# connect.net
KiCad netlist of a schematic drawn in Altium Designer
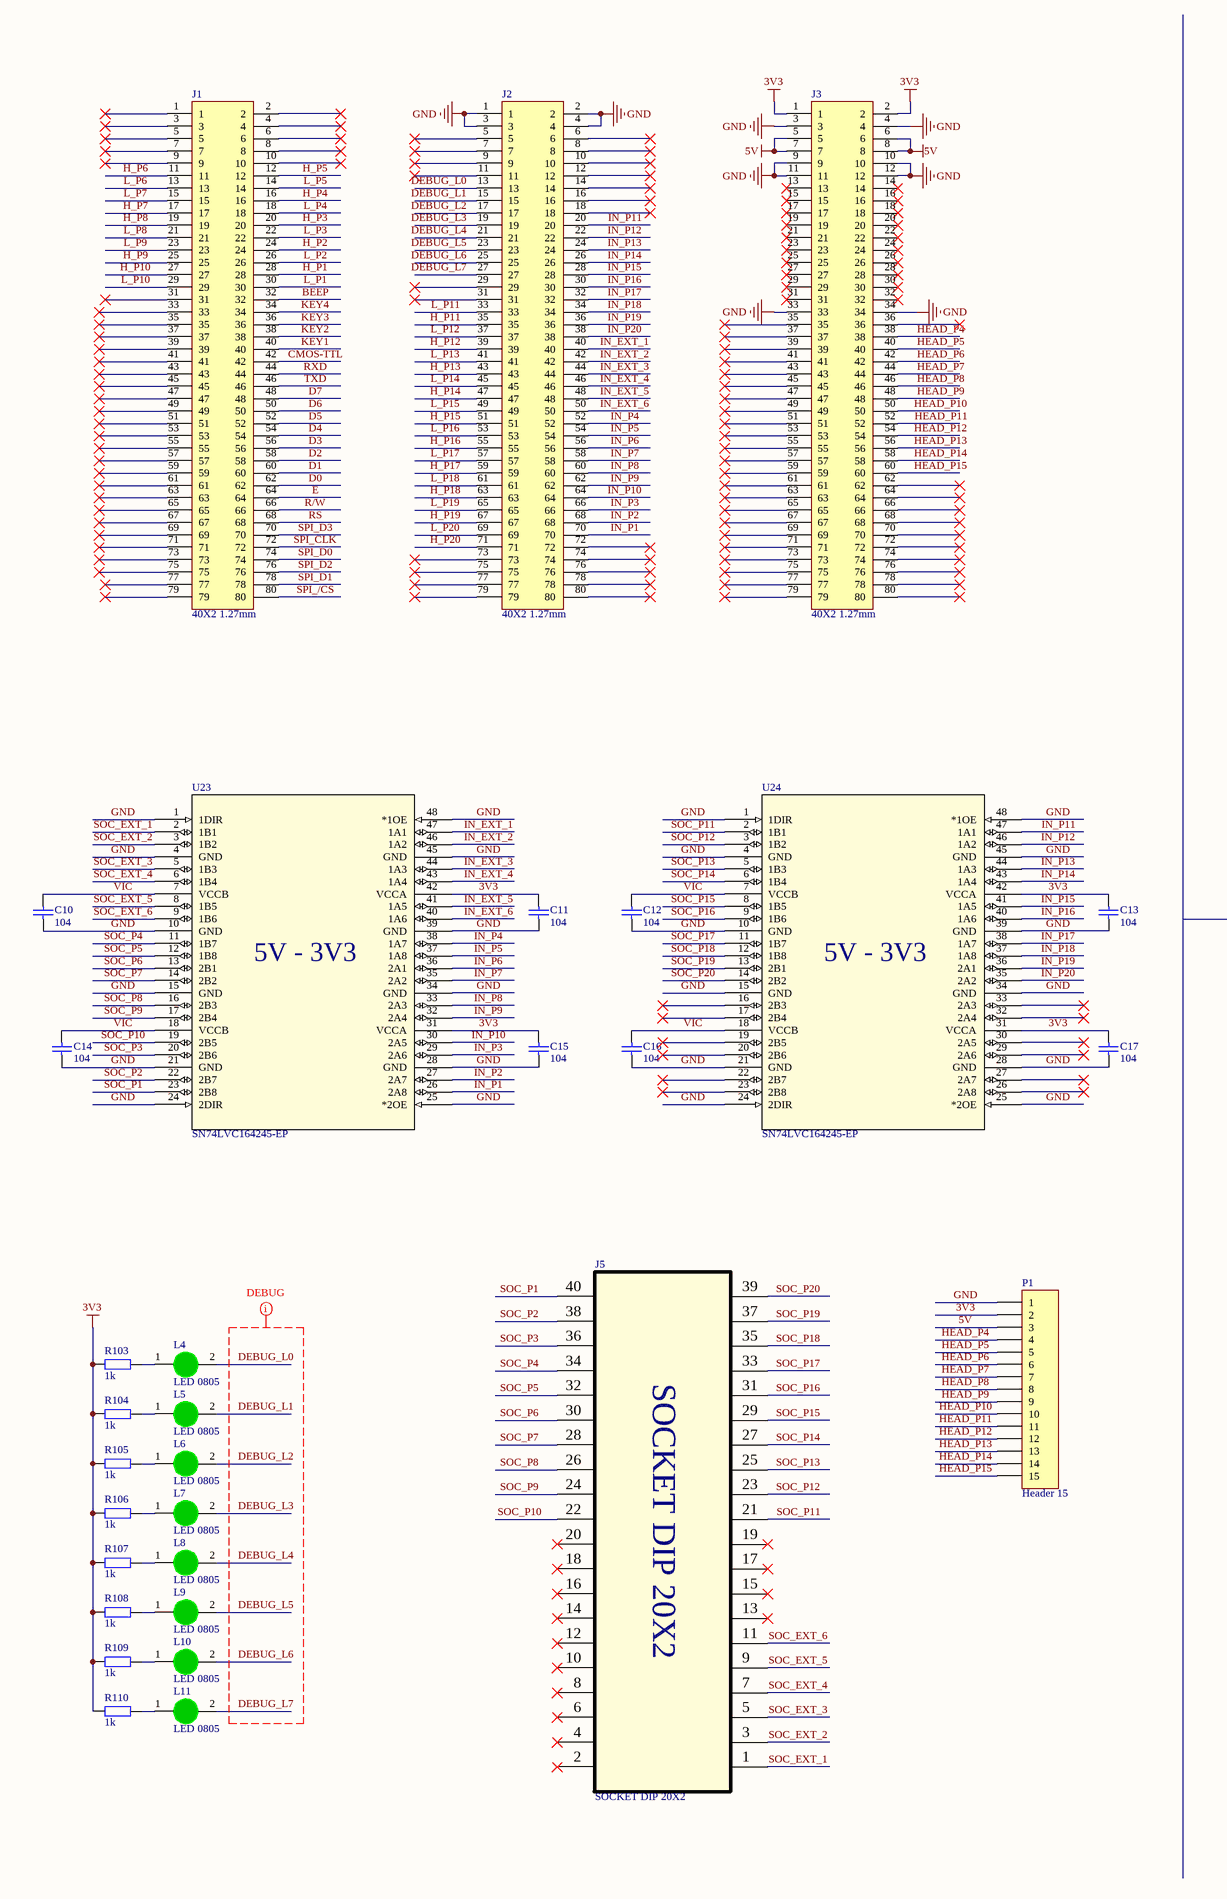
[diagram p0: connect.SchDoc, left]
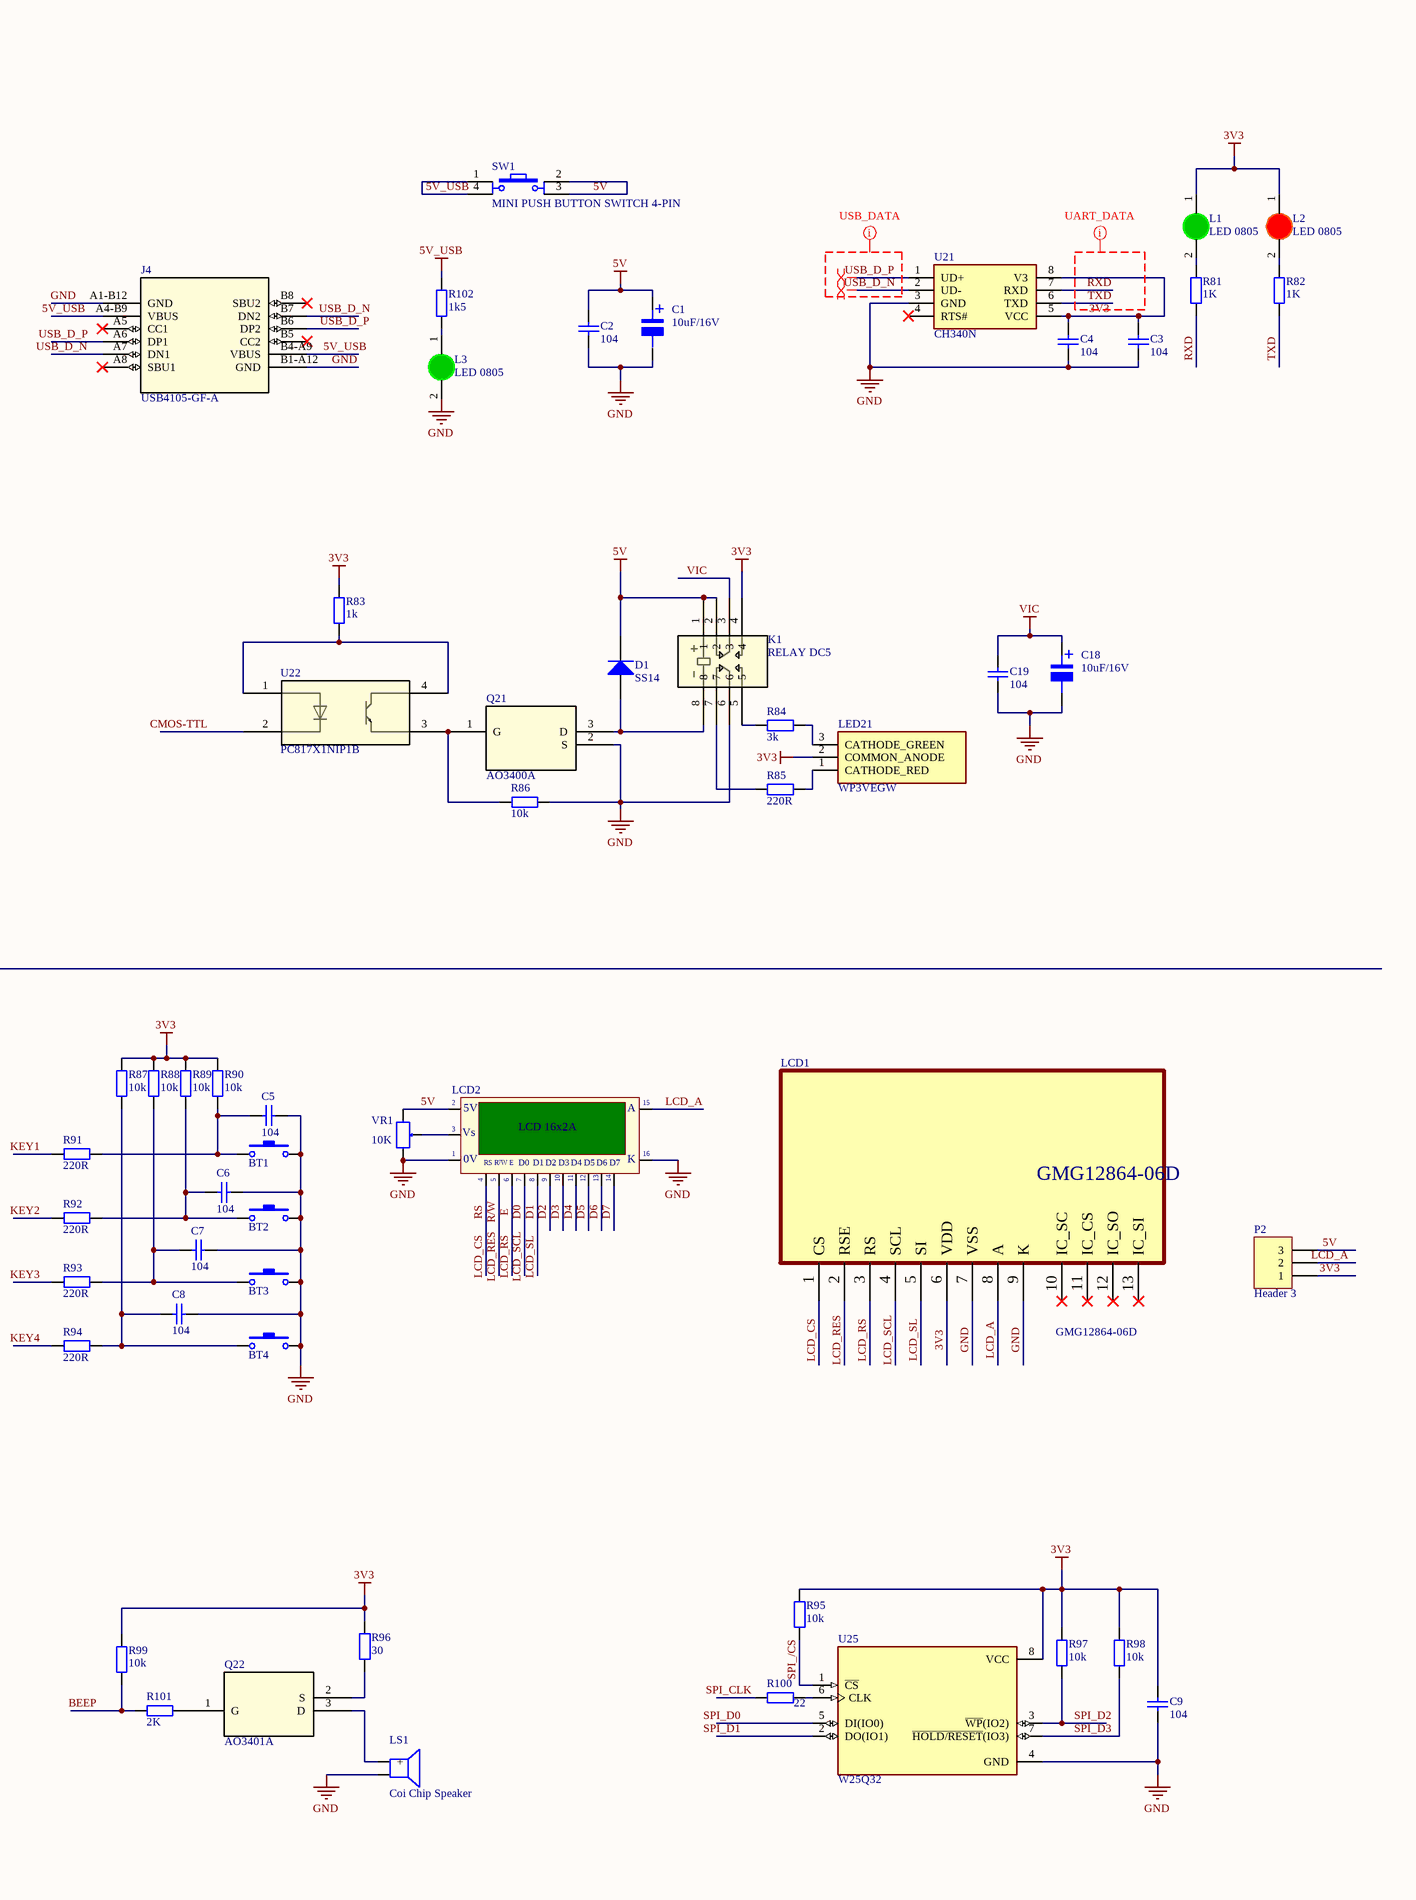
[diagram p1: connect.SchDoc, right]

(export (version "E")
  (design (tool "Eeschema 10.0.6"))
  (components
    (comp (ref "BT1")
      (value "Nut Nhan 2 Chan SMD 3x6x2.5")
      (footprint "Nut Nhan 2 Chan SMD 3x6x2.5")
      (libsource (lib "thuvien") (part "Nut Nhan 2 Chan SMD 3x6x2.5"))
    )
    (comp (ref "BT2")
      (value "Nut Nhan 2 Chan SMD 3x6x2.5")
      (footprint "Nut Nhan 2 Chan SMD 3x6x2.5")
      (libsource (lib "thuvien") (part "Nut Nhan 2 Chan SMD 3x6x2.5"))
    )
    (comp (ref "BT3")
      (value "Nut Nhan 2 Chan SMD 3x6x2.5")
      (footprint "Nut Nhan 2 Chan SMD 3x6x2.5")
      (libsource (lib "thuvien") (part "Nut Nhan 2 Chan SMD 3x6x2.5"))
    )
    (comp (ref "BT4")
      (value "Nut Nhan 2 Chan SMD 3x6x2.5")
      (footprint "Nut Nhan 2 Chan SMD 3x6x2.5")
      (libsource (lib "thuvien") (part "Nut Nhan 2 Chan SMD 3x6x2.5"))
    )
    (comp (ref "C1")
      (value "10uF/16V")
      (footprint "tu nhom 4 (b)")
      (description "Dán")
      (libsource (lib "thuvien") (part "Tu Nhom 10uF 16V"))
    )
    (comp (ref "C2")
      (value "104")
      (footprint "tu 0805")
      (description "Dán")
      (libsource (lib "thuvien") (part "Tu 0805 106 16V 10%"))
    )
    (comp (ref "C3")
      (value "104")
      (footprint "tu 0805")
      (description "Dán")
      (libsource (lib "thuvien") (part "Tu 0805 106 16V 10%"))
    )
    (comp (ref "C4")
      (value "104")
      (footprint "tu 0805")
      (description "Dán")
      (libsource (lib "thuvien") (part "Tu 0805 106 16V 10%"))
    )
    (comp (ref "C5")
      (value "104")
      (footprint "tu 0805")
      (description "Dán")
      (libsource (lib "thuvien") (part "Tu 0805 106 16V 10%"))
    )
    (comp (ref "C6")
      (value "104")
      (footprint "tu 0805")
      (description "Dán")
      (libsource (lib "thuvien") (part "Tu 0805 106 16V 10%"))
    )
    (comp (ref "C7")
      (value "104")
      (footprint "tu 0805")
      (description "Dán")
      (libsource (lib "thuvien") (part "Tu 0805 106 16V 10%"))
    )
    (comp (ref "C8")
      (value "104")
      (footprint "tu 0805")
      (description "Dán")
      (libsource (lib "thuvien") (part "Tu 0805 106 16V 10%"))
    )
    (comp (ref "C9")
      (value "104")
      (footprint "tu 0805")
      (description "Dán")
      (libsource (lib "thuvien") (part "Tu 0805 106 16V 10%"))
    )
    (comp (ref "C10")
      (value "104")
      (footprint "Tu 0805")
      (description "Dán")
      (libsource (lib "ThuVien") (part "Tu 104"))
    )
    (comp (ref "C11")
      (value "104")
      (footprint "Tu 0805")
      (description "Dán")
      (libsource (lib "ThuVien") (part "Tu 104"))
    )
    (comp (ref "C12")
      (value "104")
      (footprint "Tu 0805")
      (description "Dán")
      (libsource (lib "ThuVien") (part "Tu 104"))
    )
    (comp (ref "C13")
      (value "104")
      (footprint "Tu 0805")
      (description "Dán")
      (libsource (lib "ThuVien") (part "Tu 104"))
    )
    (comp (ref "C14")
      (value "104")
      (footprint "Tu 0805")
      (description "Dán")
      (libsource (lib "ThuVien") (part "Tu 104"))
    )
    (comp (ref "C15")
      (value "104")
      (footprint "Tu 0805")
      (description "Dán")
      (libsource (lib "ThuVien") (part "Tu 104"))
    )
    (comp (ref "C16")
      (value "104")
      (footprint "Tu 0805")
      (description "Dán")
      (libsource (lib "ThuVien") (part "Tu 104"))
    )
    (comp (ref "C17")
      (value "104")
      (footprint "Tu 0805")
      (description "Dán")
      (libsource (lib "ThuVien") (part "Tu 104"))
    )
    (comp (ref "C18")
      (value "10uF/16V")
      (footprint "tu nhom 4 (b)")
      (description "Dán")
      (libsource (lib "thuvien") (part "Tu Nhom 10uF 16V"))
    )
    (comp (ref "C19")
      (value "104")
      (footprint "tu 0805")
      (description "Dán")
      (libsource (lib "thuvien") (part "Tu 0805 106 16V 10%"))
    )
    (comp (ref "D1")
      (value "SS14")
      (footprint "DIODE SMA")
      (description "Dán")
      (libsource (lib "thuvien") (part "Diode SS14 ( 1N5819)"))
    )
    (comp (ref "J1")
      (value "40X2 1.27mm")
      (footprint "SOIC127P600X175-8N:CLP-140-02-XXX-D-A")
      (description "Connector")
      (fields (field (name "MANUFACTURER_PART_NUMBER") "CLP-140-02-G-D-A"))
      (libsource (lib "thuvien") (part "40X2 1.27mm"))
    )
    (comp (ref "J2")
      (value "40X2 1.27mm")
      (footprint "SOIC127P600X175-8N:CLP-140-02-XXX-D-A")
      (description "Connector")
      (fields (field (name "MANUFACTURER_PART_NUMBER") "CLP-140-02-G-D-A"))
      (libsource (lib "thuvien") (part "40X2 1.27mm"))
    )
    (comp (ref "J3")
      (value "40X2 1.27mm")
      (footprint "SOIC127P600X175-8N:CLP-140-02-XXX-D-A")
      (description "Connector")
      (fields (field (name "MANUFACTURER_PART_NUMBER") "CLP-140-02-G-D-A"))
      (libsource (lib "thuvien") (part "40X2 1.27mm"))
    )
    (comp (ref "J4")
      (value "USB4105-GF-A")
      (footprint "USB4105_GCT")
      (description "No Description Available")
      (fields (field (name "COPYRIGHT") "Copyright (C) 2023 Ultra Librarian. All rights reserved."))
      (libsource (lib "thuvien") (part "USB4105-GF-A"))
    )
    (comp (ref "J5")
      (value "SOCKET DIP 20X2")
      (footprint "CONN40_40-6554_ARS")
      (fields
        (field (name "MANUFACTURER_PART_NUMBER") "40-6554-10")
        (field (name "COPYRIGHT") "Copyright (C) 2023 Ultra Librarian. All rights reserved.")
      )
      (libsource (lib "thuvien") (part "SOCKET DIP 20X2"))
    )
    (comp (ref "K1")
      (value "RELAY DC5")
      (footprint "G6K-2F-Y DC3_OMR")
      (description "RELAY MINI")
      (fields
        (field (name "MANUFACTURER_PART_NUMBER") "G6K-2F-Y DC5")
        (field (name "COPYRIGHT") "Copyright (C) 2023 Ultra Librarian. All rights reserved.")
      )
      (libsource (lib "thuvien") (part "G6K-2F-Y DC5"))
    )
    (comp (ref "L1")
      (value "LED 0805")
      (footprint "LED-0805-Green")
      (description "Dán")
      (libsource (lib "thuvien") (part "LED 0805 Xanh La"))
    )
    (comp (ref "L2")
      (value "LED 0805")
      (footprint "LED-0805-Red")
      (description "Dán")
      (libsource (lib "thuvien") (part "LED 0805 Do"))
    )
    (comp (ref "L3")
      (value "LED 0805")
      (footprint "LED-0805-Green")
      (description "Dán")
      (libsource (lib "thuvien") (part "LED 0805 Xanh La"))
    )
    (comp (ref "L4")
      (value "LED 0805")
      (footprint "LED-0805-Green")
      (description "Dán")
      (libsource (lib "thuvien") (part "LED 0805 Xanh La"))
    )
    (comp (ref "L5")
      (value "LED 0805")
      (footprint "LED-0805-Green")
      (description "Dán")
      (libsource (lib "thuvien") (part "LED 0805 Xanh La"))
    )
    (comp (ref "L6")
      (value "LED 0805")
      (footprint "LED-0805-Green")
      (description "Dán")
      (libsource (lib "thuvien") (part "LED 0805 Xanh La"))
    )
    (comp (ref "L7")
      (value "LED 0805")
      (footprint "LED-0805-Green")
      (description "Dán")
      (libsource (lib "thuvien") (part "LED 0805 Xanh La"))
    )
    (comp (ref "L8")
      (value "LED 0805")
      (footprint "LED-0805-Green")
      (description "Dán")
      (libsource (lib "thuvien") (part "LED 0805 Xanh La"))
    )
    (comp (ref "L9")
      (value "LED 0805")
      (footprint "LED-0805-Green")
      (description "Dán")
      (libsource (lib "thuvien") (part "LED 0805 Xanh La"))
    )
    (comp (ref "L10")
      (value "LED 0805")
      (footprint "LED-0805-Green")
      (description "Dán")
      (libsource (lib "thuvien") (part "LED 0805 Xanh La"))
    )
    (comp (ref "L11")
      (value "LED 0805")
      (footprint "LED-0805-Green")
      (description "Dán")
      (libsource (lib "thuvien") (part "LED 0805 Xanh La"))
    )
    (comp (ref "LCD1")
      (value "GMG12864-06D")
      (footprint "GMG12864-06D")
      (fields (field (name "PUBLISHER") "Altium Limited"))
      (libsource (lib "thuvien") (part "GMG12864-06D"))
    )
    (comp (ref "LCD2")
      (value "LCD 16x2A")
      (footprint "LCD16X2N")
      (description "LCD dipslay 16 char, 2 line")
      (libsource (lib "thuvien") (part "LCD16x2A"))
    )
    (comp (ref "LED21")
      (value "WP3VEGW")
      (footprint "WP3VEGW")
      (description "LED RED/GREEN 3mm")
      (fields (field (name "MOUSER PART NUMBER") "604-WP3VEGW"))
      (libsource (lib "thuvien") (part "WP3VEGW"))
    )
    (comp (ref "LS1")
      (value "Coi Chip Speaker")
      (footprint "Coi Chip Speacker")
      (description "Còi chip")
      (libsource (lib "thuvien") (part "Coi Chip Speaker"))
    )
    (comp (ref "P1")
      (value "Header 15")
      (footprint "HDR1X15")
      (description "Header, 15-Pin")
      (fields (field (name "PUBLISHER") "Altium Limited"))
      (libsource (lib "Miscellaneous Connectors") (part "Header 15"))
    )
    (comp (ref "P2")
      (value "Header 3")
      (footprint "HDR1X3")
      (description "Header, 3-Pin")
      (fields (field (name "PUBLISHER") "Altium Limited"))
      (libsource (lib "Miscellaneous Connectors") (part "Header 3"))
    )
    (comp (ref "Q21")
      (value "AO3400A")
      (footprint "SOT-23-3L_AOS")
      (description "N-MOSFET")
      (fields (field (name "COPYRIGHT") "Copyright (C) 2023 Ultra Librarian. All rights reserved."))
      (libsource (lib "thuvien") (part "AO3400A"))
    )
    (comp (ref "Q22")
      (value "AO3401A")
      (footprint "SOT-23-3L_AOS")
      (description "P-MOSFET")
      (fields (field (name "COPYRIGHT") "Copyright (C) 2023 Ultra Librarian. All rights reserved."))
      (libsource (lib "thuvien") (part "AO3401A"))
    )
    (comp (ref "R81")
      (value "1K")
      (footprint "tro smd 0805")
      (description "Dán")
      (libsource (lib "thuvien") (part "Tro 0805 1% 10k"))
    )
    (comp (ref "R82")
      (value "1K")
      (footprint "tro smd 0805")
      (description "Dán")
      (libsource (lib "thuvien") (part "Tro 0805 1% 10k"))
    )
    (comp (ref "R83")
      (value "1k")
      (footprint "tro smd 0805")
      (description "Dán")
      (libsource (lib "thuvien") (part "Tro 0805 1% 10k"))
    )
    (comp (ref "R84")
      (value "3k")
      (footprint "tro smd 0805")
      (description "Dán")
      (libsource (lib "thuvien") (part "Tro 0805 1% 10k"))
    )
    (comp (ref "R85")
      (value "220R")
      (footprint "tro smd 0805")
      (description "Dán")
      (libsource (lib "thuvien") (part "Tro 0805 1% 10k"))
    )
    (comp (ref "R86")
      (value "10k")
      (footprint "tro smd 0805")
      (description "Dán")
      (libsource (lib "ThuVien") (part "Tro 0805 5% 10k"))
    )
    (comp (ref "R87")
      (value "10k")
      (footprint "tro smd 0805")
      (description "Dán")
      (libsource (lib "thuvien") (part "Tro 0805 1% 10k"))
    )
    (comp (ref "R88")
      (value "10k")
      (footprint "tro smd 0805")
      (description "Dán")
      (libsource (lib "thuvien") (part "Tro 0805 1% 10k"))
    )
    (comp (ref "R89")
      (value "10k")
      (footprint "tro smd 0805")
      (description "Dán")
      (libsource (lib "thuvien") (part "Tro 0805 1% 10k"))
    )
    (comp (ref "R90")
      (value "10k")
      (footprint "tro smd 0805")
      (description "Dán")
      (libsource (lib "thuvien") (part "Tro 0805 1% 10k"))
    )
    (comp (ref "R91")
      (value "220R")
      (footprint "tro smd 0805")
      (description "Dán")
      (libsource (lib "thuvien") (part "Tro 0805 1% 10k"))
    )
    (comp (ref "R92")
      (value "220R")
      (footprint "tro smd 0805")
      (description "Dán")
      (libsource (lib "thuvien") (part "Tro 0805 1% 10k"))
    )
    (comp (ref "R93")
      (value "220R")
      (footprint "tro smd 0805")
      (description "Dán")
      (libsource (lib "thuvien") (part "Tro 0805 1% 10k"))
    )
    (comp (ref "R94")
      (value "220R")
      (footprint "tro smd 0805")
      (description "Dán")
      (libsource (lib "thuvien") (part "Tro 0805 1% 10k"))
    )
    (comp (ref "R95")
      (value "10k")
      (footprint "tro smd 0805")
      (description "Dán")
      (libsource (lib "thuvien") (part "Tro 0805 1% 10k"))
    )
    (comp (ref "R96")
      (value "30")
      (footprint "tro smd 0805")
      (description "Dán")
      (libsource (lib "thuvien") (part "Tro 0805 1% 10k"))
    )
    (comp (ref "R97")
      (value "10k")
      (footprint "tro smd 0805")
      (description "Dán")
      (libsource (lib "thuvien") (part "Tro 0805 1% 10k"))
    )
    (comp (ref "R98")
      (value "10k")
      (footprint "tro smd 0805")
      (description "Dán")
      (libsource (lib "thuvien") (part "Tro 0805 1% 10k"))
    )
    (comp (ref "R99")
      (value "10k")
      (footprint "tro smd 0805")
      (description "Dán")
      (libsource (lib "thuvien") (part "Tro 0805 1% 10k"))
    )
    (comp (ref "R100")
      (value "22")
      (footprint "tro smd 0805")
      (description "Dán")
      (libsource (lib "thuvien") (part "Tro 0805 1% 10k"))
    )
    (comp (ref "R101")
      (value "2K")
      (footprint "tro smd 0805")
      (description "Dán")
      (libsource (lib "thuvien") (part "Tro 0805 1% 10k"))
    )
    (comp (ref "R102")
      (value "1k5")
      (footprint "tro smd 0805")
      (description "Dán")
      (libsource (lib "thuvien") (part "Tro 0805 1% 10k"))
    )
    (comp (ref "R103")
      (value "1k")
      (footprint "tro smd 0805")
      (description "Dán")
      (libsource (lib "thuvien") (part "Tro 0805 1% 10k"))
    )
    (comp (ref "R104")
      (value "1k")
      (footprint "tro smd 0805")
      (description "Dán")
      (libsource (lib "thuvien") (part "Tro 0805 1% 10k"))
    )
    (comp (ref "R105")
      (value "1k")
      (footprint "tro smd 0805")
      (description "Dán")
      (libsource (lib "thuvien") (part "Tro 0805 1% 10k"))
    )
    (comp (ref "R106")
      (value "1k")
      (footprint "tro smd 0805")
      (description "Dán")
      (libsource (lib "thuvien") (part "Tro 0805 1% 10k"))
    )
    (comp (ref "R107")
      (value "1k")
      (footprint "tro smd 0805")
      (description "Dán")
      (libsource (lib "thuvien") (part "Tro 0805 1% 10k"))
    )
    (comp (ref "R108")
      (value "1k")
      (footprint "tro smd 0805")
      (description "Dán")
      (libsource (lib "thuvien") (part "Tro 0805 1% 10k"))
    )
    (comp (ref "R109")
      (value "1k")
      (footprint "tro smd 0805")
      (description "Dán")
      (libsource (lib "thuvien") (part "Tro 0805 1% 10k"))
    )
    (comp (ref "R110")
      (value "1k")
      (footprint "tro smd 0805")
      (description "Dán")
      (libsource (lib "thuvien") (part "Tro 0805 1% 10k"))
    )
    (comp (ref "SW1")
      (value "MINI PUSH BUTTON SWITCH 4-PIN")
      (footprint "SW_70_31.5D47_TH_ST")
      (description "Tactile Switches MINI PUSH BUTTON SWITCH 4-PIN QTY. 4")
      (fields (field (name "MANUFACTURER") "Gravitech") (field (name "MANUFACTURER PART NUMBER") "BUTT-4"))
      (libsource (lib "thuvien") (part "SW2_BUTT-4-TH"))
    )
    (comp (ref "U21")
      (value "CH340N")
      (footprint "SOIC127P600X175-8N")
      (description "USB to TTL")
      (fields (field (name "MANUFACTURER_PART_NUMBER") "AO4606"))
      (libsource (lib "thuvien") (part "CH340N"))
    )
    (comp (ref "U22")
      (value "PC817X1NIP1B")
      (footprint "PC817XI_SHP")
      (description "cach ly quang")
      (fields (field (name "COPYRIGHT") "Copyright (C) 2023 Ultra Librarian. All rights reserved."))
      (libsource (lib "thuvien") (part "PC817X1NIP1B"))
    )
    (comp (ref "U23")
      (value "SN74LVC164245-EP")
      (footprint "DGG48")
      (description "3v3-5v, DIR enable")
      (fields
        (field (name "MANUFACTURER_PART_NUMBER") "CALVC164245MDGGREP")
        (field (name "COPYRIGHT") "Copyright (C) 2023 Ultra Librarian. All rights reserved.")
      )
      (libsource (lib "thuvien") (part "CALVC164245MDGGREP"))
    )
    (comp (ref "U24")
      (value "SN74LVC164245-EP")
      (footprint "DGG48")
      (description "3v3-5v, DIR enable")
      (fields
        (field (name "MANUFACTURER_PART_NUMBER") "CALVC164245MDGGREP")
        (field (name "COPYRIGHT") "Copyright (C) 2023 Ultra Librarian. All rights reserved.")
      )
      (libsource (lib "thuvien") (part "CALVC164245MDGGREP"))
    )
    (comp (ref "U25")
      (value "W25Q32")
      (footprint "WIN_SS-8_WIN")
      (description "3v 16m-Bit Serial Flash Memory With Dual")
      (fields
        (field (name "MF") "{'manufacturer': u'Winbond Electronics'}")
        (field (name "MP") "W25Q16JVSSIQ")
      )
      (libsource (lib "thuvien") (part "W25Q32"))
    )
    (comp (ref "VR1")
      (value "10K")
      (footprint "3362P_1")
      (description "Var Resistor")
      (libsource (lib "thuvien") (part "VR"))
    )
  )
  (nets
    (net (code "2") (name "/BEEP") (class "Default")
      (node (ref "J1") (pin "32") (pinfunction "32_32") (pintype "passive"))
      (node (ref "R101") (pin "1") (pinfunction "1_1") (pintype "passive"))
      (node (ref "R99") (pin "1") (pinfunction "1_1") (pintype "passive"))
    )
    (net (code "3") (name "/CMOS-TTL") (class "Default")
      (node (ref "J1") (pin "42") (pinfunction "42_42") (pintype "passive"))
      (node (ref "U22") (pin "2") (pinfunction "2_2") (pintype "passive"))
    )
    (net (code "4") (name "/D0") (class "Default")
      (node (ref "J1") (pin "62") (pinfunction "62_62") (pintype "passive"))
      (node (ref "LCD1") (pin "4") (pinfunction "SCL_4") (pintype "passive"))
      (node (ref "LCD2") (pin "7") (pinfunction "D0_7") (pintype "passive"))
    )
    (net (code "5") (name "/D1") (class "Default")
      (node (ref "J1") (pin "60") (pinfunction "60_60") (pintype "passive"))
      (node (ref "LCD1") (pin "5") (pinfunction "SI_5") (pintype "passive"))
      (node (ref "LCD2") (pin "8") (pinfunction "D1_8") (pintype "passive"))
    )
    (net (code "6") (name "/D2") (class "Default")
      (node (ref "J1") (pin "58") (pinfunction "58_58") (pintype "passive"))
      (node (ref "LCD2") (pin "9") (pinfunction "D2_9") (pintype "passive"))
    )
    (net (code "7") (name "/D3") (class "Default")
      (node (ref "J1") (pin "56") (pinfunction "56_56") (pintype "passive"))
      (node (ref "LCD2") (pin "10") (pinfunction "D3_10") (pintype "passive"))
    )
    (net (code "8") (name "/D4") (class "Default")
      (node (ref "J1") (pin "54") (pinfunction "54_54") (pintype "passive"))
      (node (ref "LCD2") (pin "11") (pinfunction "D4_11") (pintype "passive"))
    )
    (net (code "9") (name "/D5") (class "Default")
      (node (ref "J1") (pin "52") (pinfunction "52_52") (pintype "passive"))
      (node (ref "LCD2") (pin "12") (pinfunction "D5_12") (pintype "passive"))
    )
    (net (code "10") (name "/D6") (class "Default")
      (node (ref "J1") (pin "50") (pinfunction "50_50") (pintype "passive"))
      (node (ref "LCD2") (pin "13") (pinfunction "D6_13") (pintype "passive"))
    )
    (net (code "11") (name "/D7") (class "Default")
      (node (ref "J1") (pin "48") (pinfunction "48_48") (pintype "passive"))
      (node (ref "LCD2") (pin "14") (pinfunction "D7_14") (pintype "passive"))
    )
    (net (code "12") (name "/DEBUG_L0") (class "Default")
      (node (ref "J2") (pin "13") (pinfunction "13_13") (pintype "passive"))
      (node (ref "L4") (pin "2") (pinfunction "K_2") (pintype "passive"))
    )
    (net (code "13") (name "/DEBUG_L1") (class "Default")
      (node (ref "J2") (pin "15") (pinfunction "15_15") (pintype "passive"))
      (node (ref "L5") (pin "2") (pinfunction "K_2") (pintype "passive"))
    )
    (net (code "14") (name "/DEBUG_L2") (class "Default")
      (node (ref "J2") (pin "17") (pinfunction "17_17") (pintype "passive"))
      (node (ref "L6") (pin "2") (pinfunction "K_2") (pintype "passive"))
    )
    (net (code "15") (name "/DEBUG_L3") (class "Default")
      (node (ref "J2") (pin "19") (pinfunction "19_19") (pintype "passive"))
      (node (ref "L7") (pin "2") (pinfunction "K_2") (pintype "passive"))
    )
    (net (code "16") (name "/DEBUG_L4") (class "Default")
      (node (ref "J2") (pin "21") (pinfunction "21_21") (pintype "passive"))
      (node (ref "L8") (pin "2") (pinfunction "K_2") (pintype "passive"))
    )
    (net (code "17") (name "/DEBUG_L5") (class "Default")
      (node (ref "J2") (pin "23") (pinfunction "23_23") (pintype "passive"))
      (node (ref "L9") (pin "2") (pinfunction "K_2") (pintype "passive"))
    )
    (net (code "18") (name "/DEBUG_L6") (class "Default")
      (node (ref "J2") (pin "25") (pinfunction "25_25") (pintype "passive"))
      (node (ref "L10") (pin "2") (pinfunction "K_2") (pintype "passive"))
    )
    (net (code "19") (name "/DEBUG_L7") (class "Default")
      (node (ref "J2") (pin "27") (pinfunction "27_27") (pintype "passive"))
      (node (ref "L11") (pin "2") (pinfunction "K_2") (pintype "passive"))
    )
    (net (code "20") (name "/E") (class "Default")
      (node (ref "J1") (pin "64") (pinfunction "64_64") (pintype "passive"))
      (node (ref "LCD1") (pin "3") (pinfunction "RS_3") (pintype "passive"))
      (node (ref "LCD2") (pin "6") (pinfunction "~{EN}_6") (pintype "passive"))
    )
    (net (code "21") (name "/HEAD_P4") (class "Default")
      (node (ref "J3") (pin "38") (pinfunction "38_38") (pintype "passive"))
      (node (ref "P1") (pin "4") (pinfunction "4_4") (pintype "passive"))
    )
    (net (code "22") (name "/HEAD_P5") (class "Default")
      (node (ref "J3") (pin "40") (pinfunction "40_40") (pintype "passive"))
      (node (ref "P1") (pin "5") (pinfunction "5_5") (pintype "passive"))
    )
    (net (code "23") (name "/HEAD_P6") (class "Default")
      (node (ref "J3") (pin "42") (pinfunction "42_42") (pintype "passive"))
      (node (ref "P1") (pin "6") (pinfunction "6_6") (pintype "passive"))
    )
    (net (code "24") (name "/HEAD_P7") (class "Default")
      (node (ref "J3") (pin "44") (pinfunction "44_44") (pintype "passive"))
      (node (ref "P1") (pin "7") (pinfunction "7_7") (pintype "passive"))
    )
    (net (code "25") (name "/HEAD_P8") (class "Default")
      (node (ref "J3") (pin "46") (pinfunction "46_46") (pintype "passive"))
      (node (ref "P1") (pin "8") (pinfunction "8_8") (pintype "passive"))
    )
    (net (code "26") (name "/HEAD_P9") (class "Default")
      (node (ref "J3") (pin "48") (pinfunction "48_48") (pintype "passive"))
      (node (ref "P1") (pin "9") (pinfunction "9_9") (pintype "passive"))
    )
    (net (code "27") (name "/HEAD_P10") (class "Default")
      (node (ref "J3") (pin "50") (pinfunction "50_50") (pintype "passive"))
      (node (ref "P1") (pin "10") (pinfunction "10_10") (pintype "passive"))
    )
    (net (code "28") (name "/HEAD_P11") (class "Default")
      (node (ref "J3") (pin "52") (pinfunction "52_52") (pintype "passive"))
      (node (ref "P1") (pin "11") (pinfunction "11_11") (pintype "passive"))
    )
    (net (code "29") (name "/HEAD_P12") (class "Default")
      (node (ref "J3") (pin "54") (pinfunction "54_54") (pintype "passive"))
      (node (ref "P1") (pin "12") (pinfunction "12_12") (pintype "passive"))
    )
    (net (code "30") (name "/HEAD_P13") (class "Default")
      (node (ref "J3") (pin "56") (pinfunction "56_56") (pintype "passive"))
      (node (ref "P1") (pin "13") (pinfunction "13_13") (pintype "passive"))
    )
    (net (code "31") (name "/HEAD_P14") (class "Default")
      (node (ref "J3") (pin "58") (pinfunction "58_58") (pintype "passive"))
      (node (ref "P1") (pin "14") (pinfunction "14_14") (pintype "passive"))
    )
    (net (code "32") (name "/HEAD_P15") (class "Default")
      (node (ref "J3") (pin "60") (pinfunction "60_60") (pintype "passive"))
      (node (ref "P1") (pin "15") (pinfunction "15_15") (pintype "passive"))
    )
    (net (code "33") (name "/H_P1") (class "Default")
      (node (ref "J1") (pin "28") (pinfunction "28_28") (pintype "passive"))
    )
    (net (code "34") (name "/H_P2") (class "Default")
      (node (ref "J1") (pin "24") (pinfunction "24_24") (pintype "passive"))
    )
    (net (code "35") (name "/H_P3") (class "Default")
      (node (ref "J1") (pin "20") (pinfunction "20_20") (pintype "passive"))
    )
    (net (code "36") (name "/H_P4") (class "Default")
      (node (ref "J1") (pin "16") (pinfunction "16_16") (pintype "passive"))
    )
    (net (code "37") (name "/H_P5") (class "Default")
      (node (ref "J1") (pin "12") (pinfunction "12_12") (pintype "passive"))
    )
    (net (code "38") (name "/H_P6") (class "Default")
      (node (ref "J1") (pin "11") (pinfunction "11_11") (pintype "passive"))
    )
    (net (code "39") (name "/H_P7") (class "Default")
      (node (ref "J1") (pin "17") (pinfunction "17_17") (pintype "passive"))
    )
    (net (code "40") (name "/H_P8") (class "Default")
      (node (ref "J1") (pin "19") (pinfunction "19_19") (pintype "passive"))
    )
    (net (code "41") (name "/H_P9") (class "Default")
      (node (ref "J1") (pin "25") (pinfunction "25_25") (pintype "passive"))
    )
    (net (code "42") (name "/H_P10") (class "Default")
      (node (ref "J1") (pin "27") (pinfunction "27_27") (pintype "passive"))
    )
    (net (code "43") (name "/H_P11") (class "Default")
      (node (ref "J2") (pin "35") (pinfunction "35_35") (pintype "passive"))
    )
    (net (code "44") (name "/H_P12") (class "Default")
      (node (ref "J2") (pin "39") (pinfunction "39_39") (pintype "passive"))
    )
    (net (code "45") (name "/H_P13") (class "Default")
      (node (ref "J2") (pin "43") (pinfunction "43_43") (pintype "passive"))
    )
    (net (code "46") (name "/H_P14") (class "Default")
      (node (ref "J2") (pin "47") (pinfunction "47_47") (pintype "passive"))
    )
    (net (code "47") (name "/H_P15") (class "Default")
      (node (ref "J2") (pin "51") (pinfunction "51_51") (pintype "passive"))
    )
    (net (code "48") (name "/H_P16") (class "Default")
      (node (ref "J2") (pin "55") (pinfunction "55_55") (pintype "passive"))
    )
    (net (code "49") (name "/H_P17") (class "Default")
      (node (ref "J2") (pin "59") (pinfunction "59_59") (pintype "passive"))
    )
    (net (code "50") (name "/H_P18") (class "Default")
      (node (ref "J2") (pin "63") (pinfunction "63_63") (pintype "passive"))
    )
    (net (code "51") (name "/H_P19") (class "Default")
      (node (ref "J2") (pin "67") (pinfunction "67_67") (pintype "passive"))
    )
    (net (code "52") (name "/H_P20") (class "Default")
      (node (ref "J2") (pin "71") (pinfunction "71_71") (pintype "passive"))
    )
    (net (code "53") (name "/IN_EXT_1") (class "Default")
      (node (ref "J2") (pin "40") (pinfunction "40_40") (pintype "passive"))
      (node (ref "U23") (pin "47") (pinfunction "1A1_47") (pintype "bidirectional"))
    )
    (net (code "54") (name "/IN_EXT_2") (class "Default")
      (node (ref "J2") (pin "42") (pinfunction "42_42") (pintype "passive"))
      (node (ref "U23") (pin "46") (pinfunction "1A2_46") (pintype "bidirectional"))
    )
    (net (code "55") (name "/IN_EXT_3") (class "Default")
      (node (ref "J2") (pin "44") (pinfunction "44_44") (pintype "passive"))
      (node (ref "U23") (pin "44") (pinfunction "1A3_44") (pintype "bidirectional"))
    )
    (net (code "56") (name "/IN_EXT_4") (class "Default")
      (node (ref "J2") (pin "46") (pinfunction "46_46") (pintype "passive"))
      (node (ref "U23") (pin "43") (pinfunction "1A4_43") (pintype "bidirectional"))
    )
    (net (code "57") (name "/IN_EXT_5") (class "Default")
      (node (ref "J2") (pin "48") (pinfunction "48_48") (pintype "passive"))
      (node (ref "U23") (pin "41") (pinfunction "1A5_41") (pintype "bidirectional"))
    )
    (net (code "58") (name "/IN_EXT_6") (class "Default")
      (node (ref "J2") (pin "50") (pinfunction "50_50") (pintype "passive"))
      (node (ref "U23") (pin "40") (pinfunction "1A6_40") (pintype "bidirectional"))
    )
    (net (code "59") (name "/IN_P1") (class "Default")
      (node (ref "J2") (pin "70") (pinfunction "70_70") (pintype "passive"))
      (node (ref "U23") (pin "26") (pinfunction "2A8_26") (pintype "bidirectional"))
    )
    (net (code "60") (name "/IN_P2") (class "Default")
      (node (ref "J2") (pin "68") (pinfunction "68_68") (pintype "passive"))
      (node (ref "U23") (pin "27") (pinfunction "2A7_27") (pintype "bidirectional"))
    )
    (net (code "61") (name "/IN_P3") (class "Default")
      (node (ref "J2") (pin "66") (pinfunction "66_66") (pintype "passive"))
      (node (ref "U23") (pin "29") (pinfunction "2A6_29") (pintype "bidirectional"))
    )
    (net (code "62") (name "/IN_P4") (class "Default")
      (node (ref "J2") (pin "52") (pinfunction "52_52") (pintype "passive"))
      (node (ref "U23") (pin "38") (pinfunction "1A7_38") (pintype "bidirectional"))
    )
    (net (code "63") (name "/IN_P5") (class "Default")
      (node (ref "J2") (pin "54") (pinfunction "54_54") (pintype "passive"))
      (node (ref "U23") (pin "37") (pinfunction "1A8_37") (pintype "bidirectional"))
    )
    (net (code "64") (name "/IN_P6") (class "Default")
      (node (ref "J2") (pin "56") (pinfunction "56_56") (pintype "passive"))
      (node (ref "U23") (pin "36") (pinfunction "2A1_36") (pintype "bidirectional"))
    )
    (net (code "65") (name "/IN_P7") (class "Default")
      (node (ref "J2") (pin "58") (pinfunction "58_58") (pintype "passive"))
      (node (ref "U23") (pin "35") (pinfunction "2A2_35") (pintype "bidirectional"))
    )
    (net (code "66") (name "/IN_P8") (class "Default")
      (node (ref "J2") (pin "60") (pinfunction "60_60") (pintype "passive"))
      (node (ref "U23") (pin "33") (pinfunction "2A3_33") (pintype "bidirectional"))
    )
    (net (code "67") (name "/IN_P9") (class "Default")
      (node (ref "J2") (pin "62") (pinfunction "62_62") (pintype "passive"))
      (node (ref "U23") (pin "32") (pinfunction "2A4_32") (pintype "bidirectional"))
    )
    (net (code "68") (name "/IN_P10") (class "Default")
      (node (ref "J2") (pin "64") (pinfunction "64_64") (pintype "passive"))
      (node (ref "U23") (pin "30") (pinfunction "2A5_30") (pintype "bidirectional"))
    )
    (net (code "69") (name "/IN_P11") (class "Default")
      (node (ref "J2") (pin "20") (pinfunction "20_20") (pintype "passive"))
      (node (ref "U24") (pin "47") (pinfunction "1A1_47") (pintype "bidirectional"))
    )
    (net (code "70") (name "/IN_P12") (class "Default")
      (node (ref "J2") (pin "22") (pinfunction "22_22") (pintype "passive"))
      (node (ref "U24") (pin "46") (pinfunction "1A2_46") (pintype "bidirectional"))
    )
    (net (code "71") (name "/IN_P13") (class "Default")
      (node (ref "J2") (pin "24") (pinfunction "24_24") (pintype "passive"))
      (node (ref "U24") (pin "44") (pinfunction "1A3_44") (pintype "bidirectional"))
    )
    (net (code "72") (name "/IN_P14") (class "Default")
      (node (ref "J2") (pin "26") (pinfunction "26_26") (pintype "passive"))
      (node (ref "U24") (pin "43") (pinfunction "1A4_43") (pintype "bidirectional"))
    )
    (net (code "73") (name "/IN_P15") (class "Default")
      (node (ref "J2") (pin "28") (pinfunction "28_28") (pintype "passive"))
      (node (ref "U24") (pin "41") (pinfunction "1A5_41") (pintype "bidirectional"))
    )
    (net (code "74") (name "/IN_P16") (class "Default")
      (node (ref "J2") (pin "30") (pinfunction "30_30") (pintype "passive"))
      (node (ref "U24") (pin "40") (pinfunction "1A6_40") (pintype "bidirectional"))
    )
    (net (code "75") (name "/IN_P17") (class "Default")
      (node (ref "J2") (pin "32") (pinfunction "32_32") (pintype "passive"))
      (node (ref "U24") (pin "38") (pinfunction "1A7_38") (pintype "bidirectional"))
    )
    (net (code "76") (name "/IN_P18") (class "Default")
      (node (ref "J2") (pin "34") (pinfunction "34_34") (pintype "passive"))
      (node (ref "U24") (pin "37") (pinfunction "1A8_37") (pintype "bidirectional"))
    )
    (net (code "77") (name "/IN_P19") (class "Default")
      (node (ref "J2") (pin "36") (pinfunction "36_36") (pintype "passive"))
      (node (ref "U24") (pin "36") (pinfunction "2A1_36") (pintype "bidirectional"))
    )
    (net (code "78") (name "/IN_P20") (class "Default")
      (node (ref "J2") (pin "38") (pinfunction "38_38") (pintype "passive"))
      (node (ref "U24") (pin "35") (pinfunction "2A2_35") (pintype "bidirectional"))
    )
    (net (code "79") (name "/KEY1") (class "Default")
      (node (ref "J1") (pin "40") (pinfunction "40_40") (pintype "passive"))
      (node (ref "R91") (pin "1") (pinfunction "1_1") (pintype "passive"))
    )
    (net (code "80") (name "/KEY2") (class "Default")
      (node (ref "J1") (pin "38") (pinfunction "38_38") (pintype "passive"))
      (node (ref "R92") (pin "1") (pinfunction "1_1") (pintype "passive"))
    )
    (net (code "81") (name "/KEY3") (class "Default")
      (node (ref "J1") (pin "36") (pinfunction "36_36") (pintype "passive"))
      (node (ref "R93") (pin "1") (pinfunction "1_1") (pintype "passive"))
    )
    (net (code "82") (name "/KEY4") (class "Default")
      (node (ref "J1") (pin "34") (pinfunction "34_34") (pintype "passive"))
      (node (ref "R94") (pin "1") (pinfunction "1_1") (pintype "passive"))
    )
    (net (code "83") (name "/LCD_A") (class "Default")
      (node (ref "LCD1") (pin "8") (pinfunction "A_8") (pintype "passive"))
      (node (ref "LCD2") (pin "15") (pinfunction "A_15") (pintype "passive"))
      (node (ref "P2") (pin "2") (pinfunction "2_2") (pintype "passive"))
    )
    (net (code "84") (name "/LCD_CS") (class "Default")
      (node (ref "J1") (pin "68") (pinfunction "68_68") (pintype "passive"))
      (node (ref "LCD1") (pin "1") (pinfunction "CS_1") (pintype "passive"))
      (node (ref "LCD2") (pin "4") (pinfunction "RS_4") (pintype "passive"))
    )
    (net (code "85") (name "/LCD_RES") (class "Default")
      (node (ref "J1") (pin "66") (pinfunction "66_66") (pintype "passive"))
      (node (ref "LCD1") (pin "2") (pinfunction "RSE_2") (pintype "passive"))
      (node (ref "LCD2") (pin "5") (pinfunction "R/~{W}_5") (pintype "passive"))
    )
    (net (code "86") (name "/L_P1") (class "Default")
      (node (ref "J1") (pin "30") (pinfunction "30_30") (pintype "passive"))
    )
    (net (code "87") (name "/L_P2") (class "Default")
      (node (ref "J1") (pin "26") (pinfunction "26_26") (pintype "passive"))
    )
    (net (code "88") (name "/L_P3") (class "Default")
      (node (ref "J1") (pin "22") (pinfunction "22_22") (pintype "passive"))
    )
    (net (code "89") (name "/L_P4") (class "Default")
      (node (ref "J1") (pin "18") (pinfunction "18_18") (pintype "passive"))
    )
    (net (code "90") (name "/L_P5") (class "Default")
      (node (ref "J1") (pin "14") (pinfunction "14_14") (pintype "passive"))
    )
    (net (code "91") (name "/L_P6") (class "Default")
      (node (ref "J1") (pin "13") (pinfunction "13_13") (pintype "passive"))
    )
    (net (code "92") (name "/L_P7") (class "Default")
      (node (ref "J1") (pin "15") (pinfunction "15_15") (pintype "passive"))
    )
    (net (code "93") (name "/L_P8") (class "Default")
      (node (ref "J1") (pin "21") (pinfunction "21_21") (pintype "passive"))
    )
    (net (code "94") (name "/L_P9") (class "Default")
      (node (ref "J1") (pin "23") (pinfunction "23_23") (pintype "passive"))
    )
    (net (code "95") (name "/L_P10") (class "Default")
      (node (ref "J1") (pin "29") (pinfunction "29_29") (pintype "passive"))
    )
    (net (code "96") (name "/L_P11") (class "Default")
      (node (ref "J2") (pin "33") (pinfunction "33_33") (pintype "passive"))
    )
    (net (code "97") (name "/L_P12") (class "Default")
      (node (ref "J2") (pin "37") (pinfunction "37_37") (pintype "passive"))
    )
    (net (code "98") (name "/L_P13") (class "Default")
      (node (ref "J2") (pin "41") (pinfunction "41_41") (pintype "passive"))
    )
    (net (code "99") (name "/L_P14") (class "Default")
      (node (ref "J2") (pin "45") (pinfunction "45_45") (pintype "passive"))
    )
    (net (code "100") (name "/L_P15") (class "Default")
      (node (ref "J2") (pin "49") (pinfunction "49_49") (pintype "passive"))
    )
    (net (code "101") (name "/L_P16") (class "Default")
      (node (ref "J2") (pin "53") (pinfunction "53_53") (pintype "passive"))
    )
    (net (code "102") (name "/L_P17") (class "Default")
      (node (ref "J2") (pin "57") (pinfunction "57_57") (pintype "passive"))
    )
    (net (code "103") (name "/L_P18") (class "Default")
      (node (ref "J2") (pin "61") (pinfunction "61_61") (pintype "passive"))
    )
    (net (code "104") (name "/L_P19") (class "Default")
      (node (ref "J2") (pin "65") (pinfunction "65_65") (pintype "passive"))
    )
    (net (code "105") (name "/L_P20") (class "Default")
      (node (ref "J2") (pin "69") (pinfunction "69_69") (pintype "passive"))
    )
    (net (code "106") (name "/RXD") (class "Default")
      (node (ref "J1") (pin "44") (pinfunction "44_44") (pintype "passive"))
      (node (ref "R81") (pin "2") (pinfunction "2_2") (pintype "passive"))
      (node (ref "U21") (pin "7") (pinfunction "RXD_7") (pintype "passive"))
    )
    (net (code "107") (name "/SOC_EXT_1") (class "Default")
      (node (ref "J5") (pin "1") (pintype "passive"))
      (node (ref "U23") (pin "2") (pinfunction "1B1_2") (pintype "bidirectional"))
    )
    (net (code "108") (name "/SOC_EXT_2") (class "Default")
      (node (ref "J5") (pin "3") (pintype "passive"))
      (node (ref "U23") (pin "3") (pinfunction "1B2_3") (pintype "bidirectional"))
    )
    (net (code "109") (name "/SOC_EXT_3") (class "Default")
      (node (ref "J5") (pin "5") (pintype "passive"))
      (node (ref "U23") (pin "5") (pinfunction "1B3_5") (pintype "bidirectional"))
    )
    (net (code "110") (name "/SOC_EXT_4") (class "Default")
      (node (ref "J5") (pin "7") (pintype "passive"))
      (node (ref "U23") (pin "6") (pinfunction "1B4_6") (pintype "bidirectional"))
    )
    (net (code "111") (name "/SOC_EXT_5") (class "Default")
      (node (ref "J5") (pin "9") (pintype "passive"))
      (node (ref "U23") (pin "8") (pinfunction "1B5_8") (pintype "bidirectional"))
    )
    (net (code "112") (name "/SOC_EXT_6") (class "Default")
      (node (ref "J5") (pin "11") (pintype "passive"))
      (node (ref "U23") (pin "9") (pinfunction "1B6_9") (pintype "bidirectional"))
    )
    (net (code "113") (name "/SOC_P1") (class "Default")
      (node (ref "J5") (pin "40") (pintype "passive"))
      (node (ref "U23") (pin "23") (pinfunction "2B8_23") (pintype "bidirectional"))
    )
    (net (code "114") (name "/SOC_P2") (class "Default")
      (node (ref "J5") (pin "38") (pintype "passive"))
      (node (ref "U23") (pin "22") (pinfunction "2B7_22") (pintype "bidirectional"))
    )
    (net (code "115") (name "/SOC_P3") (class "Default")
      (node (ref "J5") (pin "36") (pintype "passive"))
      (node (ref "U23") (pin "20") (pinfunction "2B6_20") (pintype "bidirectional"))
    )
    (net (code "116") (name "/SOC_P4") (class "Default")
      (node (ref "J5") (pin "34") (pintype "passive"))
      (node (ref "U23") (pin "11") (pinfunction "1B7_11") (pintype "bidirectional"))
    )
    (net (code "117") (name "/SOC_P5") (class "Default")
      (node (ref "J5") (pin "32") (pintype "passive"))
      (node (ref "U23") (pin "12") (pinfunction "1B8_12") (pintype "bidirectional"))
    )
    (net (code "118") (name "/SOC_P6") (class "Default")
      (node (ref "J5") (pin "30") (pintype "passive"))
      (node (ref "U23") (pin "13") (pinfunction "2B1_13") (pintype "bidirectional"))
    )
    (net (code "119") (name "/SOC_P7") (class "Default")
      (node (ref "J5") (pin "28") (pintype "passive"))
      (node (ref "U23") (pin "14") (pinfunction "2B2_14") (pintype "bidirectional"))
    )
    (net (code "120") (name "/SOC_P8") (class "Default")
      (node (ref "J5") (pin "26") (pintype "passive"))
      (node (ref "U23") (pin "16") (pinfunction "2B3_16") (pintype "bidirectional"))
    )
    (net (code "121") (name "/SOC_P9") (class "Default")
      (node (ref "J5") (pin "24") (pintype "passive"))
      (node (ref "U23") (pin "17") (pinfunction "2B4_17") (pintype "bidirectional"))
    )
    (net (code "122") (name "/SOC_P10") (class "Default")
      (node (ref "J5") (pin "22") (pintype "passive"))
      (node (ref "U23") (pin "19") (pinfunction "2B5_19") (pintype "bidirectional"))
    )
    (net (code "123") (name "/SOC_P11") (class "Default")
      (node (ref "J5") (pin "21") (pintype "passive"))
      (node (ref "U24") (pin "2") (pinfunction "1B1_2") (pintype "bidirectional"))
    )
    (net (code "124") (name "/SOC_P12") (class "Default")
      (node (ref "J5") (pin "23") (pintype "passive"))
      (node (ref "U24") (pin "3") (pinfunction "1B2_3") (pintype "bidirectional"))
    )
    (net (code "125") (name "/SOC_P13") (class "Default")
      (node (ref "J5") (pin "25") (pintype "passive"))
      (node (ref "U24") (pin "5") (pinfunction "1B3_5") (pintype "bidirectional"))
    )
    (net (code "126") (name "/SOC_P14") (class "Default")
      (node (ref "J5") (pin "27") (pintype "passive"))
      (node (ref "U24") (pin "6") (pinfunction "1B4_6") (pintype "bidirectional"))
    )
    (net (code "127") (name "/SOC_P15") (class "Default")
      (node (ref "J5") (pin "29") (pintype "passive"))
      (node (ref "U24") (pin "8") (pinfunction "1B5_8") (pintype "bidirectional"))
    )
    (net (code "128") (name "/SOC_P16") (class "Default")
      (node (ref "J5") (pin "31") (pintype "passive"))
      (node (ref "U24") (pin "9") (pinfunction "1B6_9") (pintype "bidirectional"))
    )
    (net (code "129") (name "/SOC_P17") (class "Default")
      (node (ref "J5") (pin "33") (pintype "passive"))
      (node (ref "U24") (pin "11") (pinfunction "1B7_11") (pintype "bidirectional"))
    )
    (net (code "130") (name "/SOC_P18") (class "Default")
      (node (ref "J5") (pin "35") (pintype "passive"))
      (node (ref "U24") (pin "12") (pinfunction "1B8_12") (pintype "bidirectional"))
    )
    (net (code "131") (name "/SOC_P19") (class "Default")
      (node (ref "J5") (pin "37") (pintype "passive"))
      (node (ref "U24") (pin "13") (pinfunction "2B1_13") (pintype "bidirectional"))
    )
    (net (code "132") (name "/SOC_P20") (class "Default")
      (node (ref "J5") (pin "39") (pintype "passive"))
      (node (ref "U24") (pin "14") (pinfunction "2B2_14") (pintype "bidirectional"))
    )
    (net (code "133") (name "/SPI_CLK") (class "Default")
      (node (ref "J1") (pin "72") (pinfunction "72_72") (pintype "passive"))
      (node (ref "R100") (pin "2") (pinfunction "2_2") (pintype "passive"))
    )
    (net (code "134") (name "/SPI_D0") (class "Default")
      (node (ref "J1") (pin "74") (pinfunction "74_74") (pintype "passive"))
      (node (ref "U25") (pin "5") (pinfunction "DI(IO0)_5") (pintype "bidirectional"))
    )
    (net (code "135") (name "/SPI_D1") (class "Default")
      (node (ref "J1") (pin "78") (pinfunction "78_78") (pintype "passive"))
      (node (ref "U25") (pin "2") (pinfunction "DO(IO1)_2") (pintype "bidirectional"))
    )
    (net (code "136") (name "/SPI_D2") (class "Default")
      (node (ref "J1") (pin "76") (pinfunction "76_76") (pintype "passive"))
      (node (ref "R97") (pin "1") (pinfunction "1_1") (pintype "passive"))
      (node (ref "U25") (pin "3") (pinfunction "~{WP}(IO2)_3") (pintype "bidirectional"))
    )
    (net (code "137") (name "/SPI_D3") (class "Default")
      (node (ref "J1") (pin "70") (pinfunction "70_70") (pintype "passive"))
      (node (ref "R98") (pin "1") (pinfunction "1_1") (pintype "passive"))
      (node (ref "U25") (pin "7") (pinfunction "~{HOLD/RESET}(IO3)_7") (pintype "bidirectional"))
    )
    (net (code "138") (name "/SPI_{slash}CS") (class "Default")
      (node (ref "J1") (pin "80") (pinfunction "80_80") (pintype "passive"))
      (node (ref "R95") (pin "1") (pinfunction "1_1") (pintype "passive"))
      (node (ref "U25") (pin "1") (pinfunction "~{CS}_1") (pintype "input"))
    )
    (net (code "139") (name "/TXD") (class "Default")
      (node (ref "J1") (pin "46") (pinfunction "46_46") (pintype "passive"))
      (node (ref "R82") (pin "2") (pinfunction "2_2") (pintype "passive"))
      (node (ref "U21") (pin "6") (pinfunction "TXD_6") (pintype "passive"))
    )
    (net (code "140") (name "/USB_D_N") (class "Default")
      (node (ref "J4") (pin "A7") (pinfunction "DN1_A7") (pintype "bidirectional"))
      (node (ref "J4") (pin "B7") (pinfunction "DN2_B7") (pintype "bidirectional"))
      (node (ref "U21") (pin "2") (pinfunction "UD-_2") (pintype "passive"))
    )
    (net (code "141") (name "/USB_D_P") (class "Default")
      (node (ref "J4") (pin "A6") (pinfunction "DP1_A6") (pintype "bidirectional"))
      (node (ref "J4") (pin "B6") (pinfunction "DP2_B6") (pintype "bidirectional"))
      (node (ref "U21") (pin "1") (pinfunction "UD+_1") (pintype "passive"))
    )
    (net (code "142") (name "3V3") (class "Default")
      (node (ref "C11") (pin "2") (pinfunction "2_2") (pintype "passive"))
      (node (ref "C13") (pin "2") (pinfunction "2_2") (pintype "passive"))
      (node (ref "C15") (pin "2") (pinfunction "2_2") (pintype "passive"))
      (node (ref "C17") (pin "2") (pinfunction "2_2") (pintype "passive"))
      (node (ref "C3") (pin "1") (pinfunction "1_1") (pintype "passive"))
      (node (ref "C4") (pin "1") (pinfunction "1_1") (pintype "passive"))
      (node (ref "C9") (pin "1") (pinfunction "1_1") (pintype "passive"))
      (node (ref "J3") (pin "1") (pinfunction "1_1") (pintype "passive"))
      (node (ref "J3") (pin "2") (pinfunction "2_2") (pintype "passive"))
      (node (ref "K1") (pin "4") (pinfunction "4_4") (pintype "passive"))
      (node (ref "L1") (pin "1") (pinfunction "A_1") (pintype "passive"))
      (node (ref "L2") (pin "1") (pinfunction "A_1") (pintype "passive"))
      (node (ref "LCD1") (pin "6") (pinfunction "VDD_6") (pintype "passive"))
      (node (ref "LED21") (pin "2") (pinfunction "COMMON_ANODE_2") (pintype "passive"))
      (node (ref "P1") (pin "2") (pinfunction "2_2") (pintype "passive"))
      (node (ref "P2") (pin "1") (pinfunction "1_1") (pintype "passive"))
      (node (ref "R103") (pin "1") (pinfunction "1_1") (pintype "passive"))
      (node (ref "R104") (pin "1") (pinfunction "1_1") (pintype "passive"))
      (node (ref "R105") (pin "1") (pinfunction "1_1") (pintype "passive"))
      (node (ref "R106") (pin "1") (pinfunction "1_1") (pintype "passive"))
      (node (ref "R107") (pin "1") (pinfunction "1_1") (pintype "passive"))
      (node (ref "R108") (pin "1") (pinfunction "1_1") (pintype "passive"))
      (node (ref "R109") (pin "1") (pinfunction "1_1") (pintype "passive"))
      (node (ref "R110") (pin "1") (pinfunction "1_1") (pintype "passive"))
      (node (ref "R83") (pin "2") (pinfunction "2_2") (pintype "passive"))
      (node (ref "R87") (pin "2") (pinfunction "2_2") (pintype "passive"))
      (node (ref "R88") (pin "2") (pinfunction "2_2") (pintype "passive"))
      (node (ref "R89") (pin "2") (pinfunction "2_2") (pintype "passive"))
      (node (ref "R90") (pin "2") (pinfunction "2_2") (pintype "passive"))
      (node (ref "R95") (pin "2") (pinfunction "2_2") (pintype "passive"))
      (node (ref "R96") (pin "2") (pinfunction "2_2") (pintype "passive"))
      (node (ref "R97") (pin "2") (pinfunction "2_2") (pintype "passive"))
      (node (ref "R98") (pin "2") (pinfunction "2_2") (pintype "passive"))
      (node (ref "R99") (pin "2") (pinfunction "2_2") (pintype "passive"))
      (node (ref "U21") (pin "5") (pinfunction "VCC_5") (pintype "passive"))
      (node (ref "U21") (pin "8") (pinfunction "V3_8") (pintype "passive"))
      (node (ref "U23") (pin "31") (pinfunction "VCCA_31") (pintype "power_in"))
      (node (ref "U23") (pin "42") (pinfunction "VCCA_42") (pintype "power_in"))
      (node (ref "U24") (pin "31") (pinfunction "VCCA_31") (pintype "power_in"))
      (node (ref "U24") (pin "42") (pinfunction "VCCA_42") (pintype "power_in"))
      (node (ref "U25") (pin "8") (pinfunction "VCC_8") (pintype "power_in"))
    )
    (net (code "143") (name "5V") (class "Default")
      (node (ref "C1") (pin "1") (pinfunction "1_1") (pintype "passive"))
      (node (ref "C2") (pin "1") (pinfunction "1_1") (pintype "passive"))
      (node (ref "D1") (pin "2") (pinfunction "K_2") (pintype "passive"))
      (node (ref "J3") (pin "5") (pinfunction "5_5") (pintype "passive"))
      (node (ref "J3") (pin "6") (pinfunction "6_6") (pintype "passive"))
      (node (ref "J3") (pin "7") (pinfunction "7_7") (pintype "passive"))
      (node (ref "J3") (pin "8") (pinfunction "8_8") (pintype "passive"))
      (node (ref "K1") (pin "1") (pinfunction "1_1") (pintype "passive"))
      (node (ref "K1") (pin "2") (pinfunction "2_2") (pintype "passive"))
      (node (ref "LCD2") (pin "2") (pinfunction "VDD_2") (pintype "passive"))
      (node (ref "P1") (pin "3") (pinfunction "3_3") (pintype "passive"))
      (node (ref "P2") (pin "3") (pinfunction "3_3") (pintype "passive"))
      (node (ref "SW1") (pin "2") (pintype "passive"))
      (node (ref "SW1") (pin "3") (pintype "passive"))
      (node (ref "VR1") (pin "1") (pinfunction "1_1") (pintype "passive"))
    )
    (net (code "144") (name "5V_USB") (class "Default")
      (node (ref "J4") (pin "A4-B9") (pinfunction "VBUS_A4-B9") (pintype "power_in"))
      (node (ref "J4") (pin "B4-A9") (pinfunction "VBUS_B4-A9") (pintype "power_in"))
      (node (ref "R102") (pin "1") (pinfunction "1_1") (pintype "passive"))
      (node (ref "SW1") (pin "1") (pintype "passive"))
      (node (ref "SW1") (pin "4") (pintype "passive"))
    )
    (net (code "145") (name "GND") (class "Default")
      (node (ref "BT1") (pin "2") (pinfunction "2_2") (pintype "passive"))
      (node (ref "BT2") (pin "2") (pinfunction "2_2") (pintype "passive"))
      (node (ref "BT3") (pin "2") (pinfunction "2_2") (pintype "passive"))
      (node (ref "BT4") (pin "2") (pinfunction "2_2") (pintype "passive"))
      (node (ref "C1") (pin "2") (pinfunction "2_2") (pintype "passive"))
      (node (ref "C10") (pin "1") (pinfunction "1_1") (pintype "passive"))
      (node (ref "C11") (pin "1") (pinfunction "1_1") (pintype "passive"))
      (node (ref "C12") (pin "1") (pinfunction "1_1") (pintype "passive"))
      (node (ref "C13") (pin "1") (pinfunction "1_1") (pintype "passive"))
      (node (ref "C14") (pin "1") (pinfunction "1_1") (pintype "passive"))
      (node (ref "C15") (pin "1") (pinfunction "1_1") (pintype "passive"))
      (node (ref "C16") (pin "1") (pinfunction "1_1") (pintype "passive"))
      (node (ref "C17") (pin "1") (pinfunction "1_1") (pintype "passive"))
      (node (ref "C18") (pin "2") (pinfunction "2_2") (pintype "passive"))
      (node (ref "C19") (pin "2") (pinfunction "2_2") (pintype "passive"))
      (node (ref "C2") (pin "2") (pinfunction "2_2") (pintype "passive"))
      (node (ref "C3") (pin "2") (pinfunction "2_2") (pintype "passive"))
      (node (ref "C4") (pin "2") (pinfunction "2_2") (pintype "passive"))
      (node (ref "C5") (pin "1") (pinfunction "1_1") (pintype "passive"))
      (node (ref "C6") (pin "1") (pinfunction "1_1") (pintype "passive"))
      (node (ref "C7") (pin "1") (pinfunction "1_1") (pintype "passive"))
      (node (ref "C8") (pin "1") (pinfunction "1_1") (pintype "passive"))
      (node (ref "C9") (pin "2") (pinfunction "2_2") (pintype "passive"))
      (node (ref "J2") (pin "1") (pinfunction "1_1") (pintype "passive"))
      (node (ref "J2") (pin "2") (pinfunction "2_2") (pintype "passive"))
      (node (ref "J2") (pin "3") (pinfunction "3_3") (pintype "passive"))
      (node (ref "J2") (pin "4") (pinfunction "4_4") (pintype "passive"))
      (node (ref "J3") (pin "10") (pinfunction "10_10") (pintype "passive"))
      (node (ref "J3") (pin "11") (pinfunction "11_11") (pintype "passive"))
      (node (ref "J3") (pin "12") (pinfunction "12_12") (pintype "passive"))
      (node (ref "J3") (pin "3") (pinfunction "3_3") (pintype "passive"))
      (node (ref "J3") (pin "33") (pinfunction "33_33") (pintype "passive"))
      (node (ref "J3") (pin "34") (pinfunction "34_34") (pintype "passive"))
      (node (ref "J3") (pin "4") (pinfunction "4_4") (pintype "passive"))
      (node (ref "J3") (pin "9") (pinfunction "9_9") (pintype "passive"))
      (node (ref "J4") (pin "A1-B12") (pinfunction "GND_A1-B12") (pintype "power_in"))
      (node (ref "J4") (pin "B1-A12") (pinfunction "GND_B1-A12") (pintype "power_in"))
      (node (ref "K1") (pin "6") (pinfunction "6_6") (pintype "passive"))
      (node (ref "L3") (pin "2") (pinfunction "K_2") (pintype "passive"))
      (node (ref "LCD1") (pin "7") (pinfunction "VSS_7") (pintype "passive"))
      (node (ref "LCD1") (pin "9") (pinfunction "K_9") (pintype "passive"))
      (node (ref "LCD2") (pin "1") (pinfunction "GND_1") (pintype "passive"))
      (node (ref "LCD2") (pin "16") (pinfunction "K_16") (pintype "passive"))
      (node (ref "LS1") (pin "2") (pinfunction "2_2") (pintype "passive"))
      (node (ref "P1") (pin "1") (pinfunction "1_1") (pintype "passive"))
      (node (ref "Q21") (pin "2") (pinfunction "S_2") (pintype "passive"))
      (node (ref "R86") (pin "2") (pinfunction "2_2") (pintype "passive"))
      (node (ref "U21") (pin "3") (pinfunction "GND_3") (pintype "passive"))
      (node (ref "U23") (pin "1") (pinfunction "1DIR_1") (pintype "input"))
      (node (ref "U23") (pin "10") (pinfunction "GND_10") (pintype "power_in"))
      (node (ref "U23") (pin "15") (pinfunction "GND_15") (pintype "power_in"))
      (node (ref "U23") (pin "21") (pinfunction "GND_21") (pintype "power_in"))
      (node (ref "U23") (pin "24") (pinfunction "2DIR_24") (pintype "input"))
      (node (ref "U23") (pin "25") (pinfunction "*2OE_25") (pintype "input"))
      (node (ref "U23") (pin "28") (pinfunction "GND_28") (pintype "power_in"))
      (node (ref "U23") (pin "34") (pinfunction "GND_34") (pintype "power_in"))
      (node (ref "U23") (pin "39") (pinfunction "GND_39") (pintype "power_in"))
      (node (ref "U23") (pin "4") (pinfunction "GND_4") (pintype "power_in"))
      (node (ref "U23") (pin "45") (pinfunction "GND_45") (pintype "power_in"))
      (node (ref "U23") (pin "48") (pinfunction "*1OE_48") (pintype "input"))
      (node (ref "U24") (pin "1") (pinfunction "1DIR_1") (pintype "input"))
      (node (ref "U24") (pin "10") (pinfunction "GND_10") (pintype "power_in"))
      (node (ref "U24") (pin "15") (pinfunction "GND_15") (pintype "power_in"))
      (node (ref "U24") (pin "21") (pinfunction "GND_21") (pintype "power_in"))
      (node (ref "U24") (pin "24") (pinfunction "2DIR_24") (pintype "input"))
      (node (ref "U24") (pin "25") (pinfunction "*2OE_25") (pintype "input"))
      (node (ref "U24") (pin "28") (pinfunction "GND_28") (pintype "power_in"))
      (node (ref "U24") (pin "34") (pinfunction "GND_34") (pintype "power_in"))
      (node (ref "U24") (pin "39") (pinfunction "GND_39") (pintype "power_in"))
      (node (ref "U24") (pin "4") (pinfunction "GND_4") (pintype "power_in"))
      (node (ref "U24") (pin "45") (pinfunction "GND_45") (pintype "power_in"))
      (node (ref "U24") (pin "48") (pinfunction "*1OE_48") (pintype "input"))
      (node (ref "U25") (pin "4") (pinfunction "GND_4") (pintype "power_in"))
      (node (ref "VR1") (pin "3") (pinfunction "3_3") (pintype "passive"))
    )
    (net (code "146") (name "Net-(BT1-Pad1)") (class "Default")
      (node (ref "BT1") (pin "1") (pinfunction "1_1") (pintype "passive"))
      (node (ref "C5") (pin "2") (pinfunction "2_2") (pintype "passive"))
      (node (ref "R90") (pin "1") (pinfunction "1_1") (pintype "passive"))
      (node (ref "R91") (pin "2") (pinfunction "2_2") (pintype "passive"))
    )
    (net (code "147") (name "Net-(BT2-Pad1)") (class "Default")
      (node (ref "BT2") (pin "1") (pinfunction "1_1") (pintype "passive"))
      (node (ref "C6") (pin "2") (pinfunction "2_2") (pintype "passive"))
      (node (ref "R89") (pin "1") (pinfunction "1_1") (pintype "passive"))
      (node (ref "R92") (pin "2") (pinfunction "2_2") (pintype "passive"))
    )
    (net (code "148") (name "Net-(BT3-Pad1)") (class "Default")
      (node (ref "BT3") (pin "1") (pinfunction "1_1") (pintype "passive"))
      (node (ref "C7") (pin "2") (pinfunction "2_2") (pintype "passive"))
      (node (ref "R88") (pin "1") (pinfunction "1_1") (pintype "passive"))
      (node (ref "R93") (pin "2") (pinfunction "2_2") (pintype "passive"))
    )
    (net (code "149") (name "Net-(BT4-Pad1)") (class "Default")
      (node (ref "BT4") (pin "1") (pinfunction "1_1") (pintype "passive"))
      (node (ref "C8") (pin "2") (pinfunction "2_2") (pintype "passive"))
      (node (ref "R87") (pin "1") (pinfunction "1_1") (pintype "passive"))
      (node (ref "R94") (pin "2") (pinfunction "2_2") (pintype "passive"))
    )
    (net (code "150") (name "Net-(D1-A)") (class "Default")
      (node (ref "D1") (pin "1") (pinfunction "A_1") (pintype "passive"))
      (node (ref "K1") (pin "8") (pinfunction "8_8") (pintype "passive"))
      (node (ref "Q21") (pin "3") (pinfunction "D_3") (pintype "passive"))
    )
    (net (code "151") (name "Net-(K1-Pad5)") (class "Default")
      (node (ref "K1") (pin "5") (pinfunction "5_5") (pintype "passive"))
      (node (ref "R84") (pin "1") (pinfunction "1_1") (pintype "passive"))
    )
    (net (code "152") (name "Net-(K1-Pad7)") (class "Default")
      (node (ref "K1") (pin "7") (pinfunction "7_7") (pintype "passive"))
      (node (ref "R85") (pin "1") (pinfunction "1_1") (pintype "passive"))
    )
    (net (code "153") (name "Net-(L1-K)") (class "Default")
      (node (ref "L1") (pin "2") (pinfunction "K_2") (pintype "passive"))
      (node (ref "R81") (pin "1") (pinfunction "1_1") (pintype "passive"))
    )
    (net (code "154") (name "Net-(L2-K)") (class "Default")
      (node (ref "L2") (pin "2") (pinfunction "K_2") (pintype "passive"))
      (node (ref "R82") (pin "1") (pinfunction "1_1") (pintype "passive"))
    )
    (net (code "155") (name "Net-(L3-A)") (class "Default")
      (node (ref "L3") (pin "1") (pinfunction "A_1") (pintype "passive"))
      (node (ref "R102") (pin "2") (pinfunction "2_2") (pintype "passive"))
    )
    (net (code "156") (name "Net-(L4-A)") (class "Default")
      (node (ref "L4") (pin "1") (pinfunction "A_1") (pintype "passive"))
      (node (ref "R103") (pin "2") (pinfunction "2_2") (pintype "passive"))
    )
    (net (code "157") (name "Net-(L5-A)") (class "Default")
      (node (ref "L5") (pin "1") (pinfunction "A_1") (pintype "passive"))
      (node (ref "R104") (pin "2") (pinfunction "2_2") (pintype "passive"))
    )
    (net (code "158") (name "Net-(L6-A)") (class "Default")
      (node (ref "L6") (pin "1") (pinfunction "A_1") (pintype "passive"))
      (node (ref "R105") (pin "2") (pinfunction "2_2") (pintype "passive"))
    )
    (net (code "159") (name "Net-(L7-A)") (class "Default")
      (node (ref "L7") (pin "1") (pinfunction "A_1") (pintype "passive"))
      (node (ref "R106") (pin "2") (pinfunction "2_2") (pintype "passive"))
    )
    (net (code "160") (name "Net-(L8-A)") (class "Default")
      (node (ref "L8") (pin "1") (pinfunction "A_1") (pintype "passive"))
      (node (ref "R107") (pin "2") (pinfunction "2_2") (pintype "passive"))
    )
    (net (code "161") (name "Net-(L9-A)") (class "Default")
      (node (ref "L9") (pin "1") (pinfunction "A_1") (pintype "passive"))
      (node (ref "R108") (pin "2") (pinfunction "2_2") (pintype "passive"))
    )
    (net (code "162") (name "Net-(L10-A)") (class "Default")
      (node (ref "L10") (pin "1") (pinfunction "A_1") (pintype "passive"))
      (node (ref "R109") (pin "2") (pinfunction "2_2") (pintype "passive"))
    )
    (net (code "163") (name "Net-(L11-A)") (class "Default")
      (node (ref "L11") (pin "1") (pinfunction "A_1") (pintype "passive"))
      (node (ref "R110") (pin "2") (pinfunction "2_2") (pintype "passive"))
    )
    (net (code "164") (name "Net-(LCD2-VEE)") (class "Default")
      (node (ref "LCD2") (pin "3") (pinfunction "VEE_3") (pintype "passive"))
      (node (ref "VR1") (pin "2") (pinfunction "2_2") (pintype "passive"))
    )
    (net (code "165") (name "Net-(LED21-CATHODE_GREEN)") (class "Default")
      (node (ref "LED21") (pin "3") (pinfunction "CATHODE_GREEN_3") (pintype "passive"))
      (node (ref "R84") (pin "2") (pinfunction "2_2") (pintype "passive"))
    )
    (net (code "166") (name "Net-(LED21-CATHODE_RED)") (class "Default")
      (node (ref "LED21") (pin "1") (pinfunction "CATHODE_RED_1") (pintype "passive"))
      (node (ref "R85") (pin "2") (pinfunction "2_2") (pintype "passive"))
    )
    (net (code "167") (name "Net-(LS1-+)") (class "Default")
      (node (ref "LS1") (pin "1") (pinfunction "+_1") (pintype "passive"))
      (node (ref "Q22") (pin "3") (pinfunction "D_3") (pintype "passive"))
    )
    (net (code "168") (name "Net-(Q21-G)") (class "Default")
      (node (ref "Q21") (pin "1") (pinfunction "G_1") (pintype "passive"))
      (node (ref "R86") (pin "1") (pinfunction "1_1") (pintype "passive"))
      (node (ref "U22") (pin "3") (pinfunction "3_3") (pintype "passive"))
    )
    (net (code "169") (name "Net-(Q22-G)") (class "Default")
      (node (ref "Q22") (pin "1") (pinfunction "G_1") (pintype "passive"))
      (node (ref "R101") (pin "2") (pinfunction "2_2") (pintype "passive"))
    )
    (net (code "170") (name "Net-(Q22-S)") (class "Default")
      (node (ref "Q22") (pin "2") (pinfunction "S_2") (pintype "passive"))
      (node (ref "R96") (pin "1") (pinfunction "1_1") (pintype "passive"))
    )
    (net (code "171") (name "Net-(R83-Pad1)") (class "Default")
      (node (ref "R83") (pin "1") (pinfunction "1_1") (pintype "passive"))
      (node (ref "U22") (pin "1") (pinfunction "1_1") (pintype "passive"))
      (node (ref "U22") (pin "4") (pinfunction "4_4") (pintype "passive"))
    )
    (net (code "172") (name "Net-(U25-CLK)") (class "Default")
      (node (ref "R100") (pin "1") (pinfunction "1_1") (pintype "passive"))
      (node (ref "U25") (pin "6") (pinfunction "CLK_6") (pintype "input"))
    )
    (net (code "173") (name "VIC") (class "Default")
      (node (ref "C10") (pin "2") (pinfunction "2_2") (pintype "passive"))
      (node (ref "C12") (pin "2") (pinfunction "2_2") (pintype "passive"))
      (node (ref "C14") (pin "2") (pinfunction "2_2") (pintype "passive"))
      (node (ref "C16") (pin "2") (pinfunction "2_2") (pintype "passive"))
      (node (ref "C18") (pin "1") (pinfunction "1_1") (pintype "passive"))
      (node (ref "C19") (pin "1") (pinfunction "1_1") (pintype "passive"))
      (node (ref "K1") (pin "3") (pinfunction "3_3") (pintype "passive"))
      (node (ref "U23") (pin "18") (pinfunction "VCCB_18") (pintype "power_in"))
      (node (ref "U23") (pin "7") (pinfunction "VCCB_7") (pintype "power_in"))
      (node (ref "U24") (pin "18") (pinfunction "VCCB_18") (pintype "power_in"))
      (node (ref "U24") (pin "7") (pinfunction "VCCB_7") (pintype "power_in"))
    )
    (net (code "174") (name "unconnected-(J1-Pad1)") (class "Default")
      (node (ref "J1") (pin "1") (pinfunction "1_1") (pintype "passive+no_connect"))
    )
    (net (code "175") (name "unconnected-(J1-Pad2)") (class "Default")
      (node (ref "J1") (pin "2") (pinfunction "2_2") (pintype "passive+no_connect"))
    )
    (net (code "176") (name "unconnected-(J1-Pad3)") (class "Default")
      (node (ref "J1") (pin "3") (pinfunction "3_3") (pintype "passive+no_connect"))
    )
    (net (code "177") (name "unconnected-(J1-Pad4)") (class "Default")
      (node (ref "J1") (pin "4") (pinfunction "4_4") (pintype "passive+no_connect"))
    )
    (net (code "178") (name "unconnected-(J1-Pad5)") (class "Default")
      (node (ref "J1") (pin "5") (pinfunction "5_5") (pintype "passive+no_connect"))
    )
    (net (code "179") (name "unconnected-(J1-Pad6)") (class "Default")
      (node (ref "J1") (pin "6") (pinfunction "6_6") (pintype "passive+no_connect"))
    )
    (net (code "180") (name "unconnected-(J1-Pad7)") (class "Default")
      (node (ref "J1") (pin "7") (pinfunction "7_7") (pintype "passive+no_connect"))
    )
    (net (code "181") (name "unconnected-(J1-Pad8)") (class "Default")
      (node (ref "J1") (pin "8") (pinfunction "8_8") (pintype "passive+no_connect"))
    )
    (net (code "182") (name "unconnected-(J1-Pad9)") (class "Default")
      (node (ref "J1") (pin "9") (pinfunction "9_9") (pintype "passive+no_connect"))
    )
    (net (code "183") (name "unconnected-(J1-Pad10)") (class "Default")
      (node (ref "J1") (pin "10") (pinfunction "10_10") (pintype "passive+no_connect"))
    )
    (net (code "184") (name "unconnected-(J1-Pad31)") (class "Default")
      (node (ref "J1") (pin "31") (pinfunction "31_31") (pintype "passive+no_connect"))
    )
    (net (code "185") (name "unconnected-(J1-Pad33)") (class "Default")
      (node (ref "J1") (pin "33") (pinfunction "33_33") (pintype "passive+no_connect"))
    )
    (net (code "186") (name "unconnected-(J1-Pad35)") (class "Default")
      (node (ref "J1") (pin "35") (pinfunction "35_35") (pintype "passive+no_connect"))
    )
    (net (code "187") (name "unconnected-(J1-Pad37)") (class "Default")
      (node (ref "J1") (pin "37") (pinfunction "37_37") (pintype "passive+no_connect"))
    )
    (net (code "188") (name "unconnected-(J1-Pad39)") (class "Default")
      (node (ref "J1") (pin "39") (pinfunction "39_39") (pintype "passive+no_connect"))
    )
    (net (code "189") (name "unconnected-(J1-Pad41)") (class "Default")
      (node (ref "J1") (pin "41") (pinfunction "41_41") (pintype "passive+no_connect"))
    )
    (net (code "190") (name "unconnected-(J1-Pad43)") (class "Default")
      (node (ref "J1") (pin "43") (pinfunction "43_43") (pintype "passive+no_connect"))
    )
    (net (code "191") (name "unconnected-(J1-Pad45)") (class "Default")
      (node (ref "J1") (pin "45") (pinfunction "45_45") (pintype "passive+no_connect"))
    )
    (net (code "192") (name "unconnected-(J1-Pad47)") (class "Default")
      (node (ref "J1") (pin "47") (pinfunction "47_47") (pintype "passive+no_connect"))
    )
    (net (code "193") (name "unconnected-(J1-Pad49)") (class "Default")
      (node (ref "J1") (pin "49") (pinfunction "49_49") (pintype "passive+no_connect"))
    )
    (net (code "194") (name "unconnected-(J1-Pad51)") (class "Default")
      (node (ref "J1") (pin "51") (pinfunction "51_51") (pintype "passive+no_connect"))
    )
    (net (code "195") (name "unconnected-(J1-Pad53)") (class "Default")
      (node (ref "J1") (pin "53") (pinfunction "53_53") (pintype "passive+no_connect"))
    )
    (net (code "196") (name "unconnected-(J1-Pad55)") (class "Default")
      (node (ref "J1") (pin "55") (pinfunction "55_55") (pintype "passive+no_connect"))
    )
    (net (code "197") (name "unconnected-(J1-Pad57)") (class "Default")
      (node (ref "J1") (pin "57") (pinfunction "57_57") (pintype "passive+no_connect"))
    )
    (net (code "198") (name "unconnected-(J1-Pad59)") (class "Default")
      (node (ref "J1") (pin "59") (pinfunction "59_59") (pintype "passive+no_connect"))
    )
    (net (code "199") (name "unconnected-(J1-Pad61)") (class "Default")
      (node (ref "J1") (pin "61") (pinfunction "61_61") (pintype "passive+no_connect"))
    )
    (net (code "200") (name "unconnected-(J1-Pad63)") (class "Default")
      (node (ref "J1") (pin "63") (pinfunction "63_63") (pintype "passive+no_connect"))
    )
    (net (code "201") (name "unconnected-(J1-Pad65)") (class "Default")
      (node (ref "J1") (pin "65") (pinfunction "65_65") (pintype "passive+no_connect"))
    )
    (net (code "202") (name "unconnected-(J1-Pad67)") (class "Default")
      (node (ref "J1") (pin "67") (pinfunction "67_67") (pintype "passive+no_connect"))
    )
    (net (code "203") (name "unconnected-(J1-Pad69)") (class "Default")
      (node (ref "J1") (pin "69") (pinfunction "69_69") (pintype "passive+no_connect"))
    )
    (net (code "204") (name "unconnected-(J1-Pad71)") (class "Default")
      (node (ref "J1") (pin "71") (pinfunction "71_71") (pintype "passive+no_connect"))
    )
    (net (code "205") (name "unconnected-(J1-Pad73)") (class "Default")
      (node (ref "J1") (pin "73") (pinfunction "73_73") (pintype "passive+no_connect"))
    )
    (net (code "206") (name "unconnected-(J1-Pad75)") (class "Default")
      (node (ref "J1") (pin "75") (pinfunction "75_75") (pintype "passive+no_connect"))
    )
    (net (code "207") (name "unconnected-(J1-Pad77)") (class "Default")
      (node (ref "J1") (pin "77") (pinfunction "77_77") (pintype "passive+no_connect"))
    )
    (net (code "208") (name "unconnected-(J1-Pad79)") (class "Default")
      (node (ref "J1") (pin "79") (pinfunction "79_79") (pintype "passive+no_connect"))
    )
    (net (code "209") (name "unconnected-(J2-Pad5)") (class "Default")
      (node (ref "J2") (pin "5") (pinfunction "5_5") (pintype "passive+no_connect"))
    )
    (net (code "210") (name "unconnected-(J2-Pad6)") (class "Default")
      (node (ref "J2") (pin "6") (pinfunction "6_6") (pintype "passive+no_connect"))
    )
    (net (code "211") (name "unconnected-(J2-Pad7)") (class "Default")
      (node (ref "J2") (pin "7") (pinfunction "7_7") (pintype "passive+no_connect"))
    )
    (net (code "212") (name "unconnected-(J2-Pad8)") (class "Default")
      (node (ref "J2") (pin "8") (pinfunction "8_8") (pintype "passive+no_connect"))
    )
    (net (code "213") (name "unconnected-(J2-Pad9)") (class "Default")
      (node (ref "J2") (pin "9") (pinfunction "9_9") (pintype "passive+no_connect"))
    )
    (net (code "214") (name "unconnected-(J2-Pad10)") (class "Default")
      (node (ref "J2") (pin "10") (pinfunction "10_10") (pintype "passive+no_connect"))
    )
    (net (code "215") (name "unconnected-(J2-Pad11)") (class "Default")
      (node (ref "J2") (pin "11") (pinfunction "11_11") (pintype "passive+no_connect"))
    )
    (net (code "216") (name "unconnected-(J2-Pad12)") (class "Default")
      (node (ref "J2") (pin "12") (pinfunction "12_12") (pintype "passive+no_connect"))
    )
    (net (code "217") (name "unconnected-(J2-Pad14)") (class "Default")
      (node (ref "J2") (pin "14") (pinfunction "14_14") (pintype "passive+no_connect"))
    )
    (net (code "218") (name "unconnected-(J2-Pad16)") (class "Default")
      (node (ref "J2") (pin "16") (pinfunction "16_16") (pintype "passive+no_connect"))
    )
    (net (code "219") (name "unconnected-(J2-Pad18)") (class "Default")
      (node (ref "J2") (pin "18") (pinfunction "18_18") (pintype "passive+no_connect"))
    )
    (net (code "220") (name "unconnected-(J2-Pad29)") (class "Default")
      (node (ref "J2") (pin "29") (pinfunction "29_29") (pintype "passive+no_connect"))
    )
    (net (code "221") (name "unconnected-(J2-Pad31)") (class "Default")
      (node (ref "J2") (pin "31") (pinfunction "31_31") (pintype "passive+no_connect"))
    )
    (net (code "222") (name "unconnected-(J2-Pad72)") (class "Default")
      (node (ref "J2") (pin "72") (pinfunction "72_72") (pintype "passive+no_connect"))
    )
    (net (code "223") (name "unconnected-(J2-Pad73)") (class "Default")
      (node (ref "J2") (pin "73") (pinfunction "73_73") (pintype "passive+no_connect"))
    )
    (net (code "224") (name "unconnected-(J2-Pad74)") (class "Default")
      (node (ref "J2") (pin "74") (pinfunction "74_74") (pintype "passive+no_connect"))
    )
    (net (code "225") (name "unconnected-(J2-Pad75)") (class "Default")
      (node (ref "J2") (pin "75") (pinfunction "75_75") (pintype "passive+no_connect"))
    )
    (net (code "226") (name "unconnected-(J2-Pad76)") (class "Default")
      (node (ref "J2") (pin "76") (pinfunction "76_76") (pintype "passive+no_connect"))
    )
    (net (code "227") (name "unconnected-(J2-Pad77)") (class "Default")
      (node (ref "J2") (pin "77") (pinfunction "77_77") (pintype "passive+no_connect"))
    )
    (net (code "228") (name "unconnected-(J2-Pad78)") (class "Default")
      (node (ref "J2") (pin "78") (pinfunction "78_78") (pintype "passive+no_connect"))
    )
    (net (code "229") (name "unconnected-(J2-Pad79)") (class "Default")
      (node (ref "J2") (pin "79") (pinfunction "79_79") (pintype "passive+no_connect"))
    )
    (net (code "230") (name "unconnected-(J2-Pad80)") (class "Default")
      (node (ref "J2") (pin "80") (pinfunction "80_80") (pintype "passive+no_connect"))
    )
    (net (code "231") (name "unconnected-(J3-Pad13)") (class "Default")
      (node (ref "J3") (pin "13") (pinfunction "13_13") (pintype "passive+no_connect"))
    )
    (net (code "232") (name "unconnected-(J3-Pad14)") (class "Default")
      (node (ref "J3") (pin "14") (pinfunction "14_14") (pintype "passive+no_connect"))
    )
    (net (code "233") (name "unconnected-(J3-Pad15)") (class "Default")
      (node (ref "J3") (pin "15") (pinfunction "15_15") (pintype "passive+no_connect"))
    )
    (net (code "234") (name "unconnected-(J3-Pad16)") (class "Default")
      (node (ref "J3") (pin "16") (pinfunction "16_16") (pintype "passive+no_connect"))
    )
    (net (code "235") (name "unconnected-(J3-Pad17)") (class "Default")
      (node (ref "J3") (pin "17") (pinfunction "17_17") (pintype "passive+no_connect"))
    )
    (net (code "236") (name "unconnected-(J3-Pad18)") (class "Default")
      (node (ref "J3") (pin "18") (pinfunction "18_18") (pintype "passive+no_connect"))
    )
    (net (code "237") (name "unconnected-(J3-Pad19)") (class "Default")
      (node (ref "J3") (pin "19") (pinfunction "19_19") (pintype "passive+no_connect"))
    )
    (net (code "238") (name "unconnected-(J3-Pad20)") (class "Default")
      (node (ref "J3") (pin "20") (pinfunction "20_20") (pintype "passive+no_connect"))
    )
    (net (code "239") (name "unconnected-(J3-Pad21)") (class "Default")
      (node (ref "J3") (pin "21") (pinfunction "21_21") (pintype "passive+no_connect"))
    )
    (net (code "240") (name "unconnected-(J3-Pad22)") (class "Default")
      (node (ref "J3") (pin "22") (pinfunction "22_22") (pintype "passive+no_connect"))
    )
    (net (code "241") (name "unconnected-(J3-Pad23)") (class "Default")
      (node (ref "J3") (pin "23") (pinfunction "23_23") (pintype "passive+no_connect"))
    )
    (net (code "242") (name "unconnected-(J3-Pad24)") (class "Default")
      (node (ref "J3") (pin "24") (pinfunction "24_24") (pintype "passive+no_connect"))
    )
    (net (code "243") (name "unconnected-(J3-Pad25)") (class "Default")
      (node (ref "J3") (pin "25") (pinfunction "25_25") (pintype "passive+no_connect"))
    )
    (net (code "244") (name "unconnected-(J3-Pad26)") (class "Default")
      (node (ref "J3") (pin "26") (pinfunction "26_26") (pintype "passive+no_connect"))
    )
    (net (code "245") (name "unconnected-(J3-Pad27)") (class "Default")
      (node (ref "J3") (pin "27") (pinfunction "27_27") (pintype "passive+no_connect"))
    )
    (net (code "246") (name "unconnected-(J3-Pad28)") (class "Default")
      (node (ref "J3") (pin "28") (pinfunction "28_28") (pintype "passive+no_connect"))
    )
    (net (code "247") (name "unconnected-(J3-Pad29)") (class "Default")
      (node (ref "J3") (pin "29") (pinfunction "29_29") (pintype "passive+no_connect"))
    )
    (net (code "248") (name "unconnected-(J3-Pad30)") (class "Default")
      (node (ref "J3") (pin "30") (pinfunction "30_30") (pintype "passive+no_connect"))
    )
    (net (code "249") (name "unconnected-(J3-Pad31)") (class "Default")
      (node (ref "J3") (pin "31") (pinfunction "31_31") (pintype "passive+no_connect"))
    )
    (net (code "250") (name "unconnected-(J3-Pad32)") (class "Default")
      (node (ref "J3") (pin "32") (pinfunction "32_32") (pintype "passive+no_connect"))
    )
    (net (code "251") (name "unconnected-(J3-Pad35)") (class "Default")
      (node (ref "J3") (pin "35") (pinfunction "35_35") (pintype "passive+no_connect"))
    )
    (net (code "252") (name "unconnected-(J3-Pad36)") (class "Default")
      (node (ref "J3") (pin "36") (pinfunction "36_36") (pintype "passive+no_connect"))
    )
    (net (code "253") (name "unconnected-(J3-Pad37)") (class "Default")
      (node (ref "J3") (pin "37") (pinfunction "37_37") (pintype "passive+no_connect"))
    )
    (net (code "254") (name "unconnected-(J3-Pad39)") (class "Default")
      (node (ref "J3") (pin "39") (pinfunction "39_39") (pintype "passive+no_connect"))
    )
    (net (code "255") (name "unconnected-(J3-Pad41)") (class "Default")
      (node (ref "J3") (pin "41") (pinfunction "41_41") (pintype "passive+no_connect"))
    )
    (net (code "256") (name "unconnected-(J3-Pad43)") (class "Default")
      (node (ref "J3") (pin "43") (pinfunction "43_43") (pintype "passive+no_connect"))
    )
    (net (code "257") (name "unconnected-(J3-Pad45)") (class "Default")
      (node (ref "J3") (pin "45") (pinfunction "45_45") (pintype "passive+no_connect"))
    )
    (net (code "258") (name "unconnected-(J3-Pad47)") (class "Default")
      (node (ref "J3") (pin "47") (pinfunction "47_47") (pintype "passive+no_connect"))
    )
    (net (code "259") (name "unconnected-(J3-Pad49)") (class "Default")
      (node (ref "J3") (pin "49") (pinfunction "49_49") (pintype "passive+no_connect"))
    )
    (net (code "260") (name "unconnected-(J3-Pad51)") (class "Default")
      (node (ref "J3") (pin "51") (pinfunction "51_51") (pintype "passive+no_connect"))
    )
    (net (code "261") (name "unconnected-(J3-Pad53)") (class "Default")
      (node (ref "J3") (pin "53") (pinfunction "53_53") (pintype "passive+no_connect"))
    )
    (net (code "262") (name "unconnected-(J3-Pad55)") (class "Default")
      (node (ref "J3") (pin "55") (pinfunction "55_55") (pintype "passive+no_connect"))
    )
    (net (code "263") (name "unconnected-(J3-Pad57)") (class "Default")
      (node (ref "J3") (pin "57") (pinfunction "57_57") (pintype "passive+no_connect"))
    )
    (net (code "264") (name "unconnected-(J3-Pad59)") (class "Default")
      (node (ref "J3") (pin "59") (pinfunction "59_59") (pintype "passive+no_connect"))
    )
    (net (code "265") (name "unconnected-(J3-Pad61)") (class "Default")
      (node (ref "J3") (pin "61") (pinfunction "61_61") (pintype "passive+no_connect"))
    )
    (net (code "266") (name "unconnected-(J3-Pad62)") (class "Default")
      (node (ref "J3") (pin "62") (pinfunction "62_62") (pintype "passive+no_connect"))
    )
    (net (code "267") (name "unconnected-(J3-Pad63)") (class "Default")
      (node (ref "J3") (pin "63") (pinfunction "63_63") (pintype "passive+no_connect"))
    )
    (net (code "268") (name "unconnected-(J3-Pad64)") (class "Default")
      (node (ref "J3") (pin "64") (pinfunction "64_64") (pintype "passive+no_connect"))
    )
    (net (code "269") (name "unconnected-(J3-Pad65)") (class "Default")
      (node (ref "J3") (pin "65") (pinfunction "65_65") (pintype "passive+no_connect"))
    )
    (net (code "270") (name "unconnected-(J3-Pad66)") (class "Default")
      (node (ref "J3") (pin "66") (pinfunction "66_66") (pintype "passive+no_connect"))
    )
    (net (code "271") (name "unconnected-(J3-Pad67)") (class "Default")
      (node (ref "J3") (pin "67") (pinfunction "67_67") (pintype "passive+no_connect"))
    )
    (net (code "272") (name "unconnected-(J3-Pad68)") (class "Default")
      (node (ref "J3") (pin "68") (pinfunction "68_68") (pintype "passive+no_connect"))
    )
    (net (code "273") (name "unconnected-(J3-Pad69)") (class "Default")
      (node (ref "J3") (pin "69") (pinfunction "69_69") (pintype "passive+no_connect"))
    )
    (net (code "274") (name "unconnected-(J3-Pad70)") (class "Default")
      (node (ref "J3") (pin "70") (pinfunction "70_70") (pintype "passive+no_connect"))
    )
    (net (code "275") (name "unconnected-(J3-Pad71)") (class "Default")
      (node (ref "J3") (pin "71") (pinfunction "71_71") (pintype "passive+no_connect"))
    )
    (net (code "276") (name "unconnected-(J3-Pad72)") (class "Default")
      (node (ref "J3") (pin "72") (pinfunction "72_72") (pintype "passive+no_connect"))
    )
    (net (code "277") (name "unconnected-(J3-Pad73)") (class "Default")
      (node (ref "J3") (pin "73") (pinfunction "73_73") (pintype "passive+no_connect"))
    )
    (net (code "278") (name "unconnected-(J3-Pad74)") (class "Default")
      (node (ref "J3") (pin "74") (pinfunction "74_74") (pintype "passive+no_connect"))
    )
    (net (code "279") (name "unconnected-(J3-Pad75)") (class "Default")
      (node (ref "J3") (pin "75") (pinfunction "75_75") (pintype "passive+no_connect"))
    )
    (net (code "280") (name "unconnected-(J3-Pad76)") (class "Default")
      (node (ref "J3") (pin "76") (pinfunction "76_76") (pintype "passive+no_connect"))
    )
    (net (code "281") (name "unconnected-(J3-Pad77)") (class "Default")
      (node (ref "J3") (pin "77") (pinfunction "77_77") (pintype "passive+no_connect"))
    )
    (net (code "282") (name "unconnected-(J3-Pad78)") (class "Default")
      (node (ref "J3") (pin "78") (pinfunction "78_78") (pintype "passive+no_connect"))
    )
    (net (code "283") (name "unconnected-(J3-Pad79)") (class "Default")
      (node (ref "J3") (pin "79") (pinfunction "79_79") (pintype "passive+no_connect"))
    )
    (net (code "284") (name "unconnected-(J3-Pad80)") (class "Default")
      (node (ref "J3") (pin "80") (pinfunction "80_80") (pintype "passive+no_connect"))
    )
    (net (code "285") (name "unconnected-(J4-CC1-PadA5)") (class "Default")
      (node (ref "J4") (pin "A5") (pinfunction "CC1_A5") (pintype "bidirectional+no_connect"))
    )
    (net (code "286") (name "unconnected-(J4-CC2-PadB5)") (class "Default")
      (node (ref "J4") (pin "B5") (pinfunction "CC2_B5") (pintype "bidirectional+no_connect"))
    )
    (net (code "287") (name "unconnected-(J4-SBU1-PadA8)") (class "Default")
      (node (ref "J4") (pin "A8") (pinfunction "SBU1_A8") (pintype "bidirectional+no_connect"))
    )
    (net (code "288") (name "unconnected-(J4-SBU2-PadB8)") (class "Default")
      (node (ref "J4") (pin "B8") (pinfunction "SBU2_B8") (pintype "bidirectional+no_connect"))
    )
    (net (code "289") (name "unconnected-(J5-Pad2)") (class "Default")
      (node (ref "J5") (pin "2") (pintype "passive+no_connect"))
    )
    (net (code "290") (name "unconnected-(J5-Pad4)") (class "Default")
      (node (ref "J5") (pin "4") (pintype "passive+no_connect"))
    )
    (net (code "291") (name "unconnected-(J5-Pad6)") (class "Default")
      (node (ref "J5") (pin "6") (pintype "passive+no_connect"))
    )
    (net (code "292") (name "unconnected-(J5-Pad8)") (class "Default")
      (node (ref "J5") (pin "8") (pintype "passive+no_connect"))
    )
    (net (code "293") (name "unconnected-(J5-Pad10)") (class "Default")
      (node (ref "J5") (pin "10") (pintype "passive+no_connect"))
    )
    (net (code "294") (name "unconnected-(J5-Pad12)") (class "Default")
      (node (ref "J5") (pin "12") (pintype "passive+no_connect"))
    )
    (net (code "295") (name "unconnected-(J5-Pad13)") (class "Default")
      (node (ref "J5") (pin "13") (pintype "passive+no_connect"))
    )
    (net (code "296") (name "unconnected-(J5-Pad14)") (class "Default")
      (node (ref "J5") (pin "14") (pintype "passive+no_connect"))
    )
    (net (code "297") (name "unconnected-(J5-Pad15)") (class "Default")
      (node (ref "J5") (pin "15") (pintype "passive+no_connect"))
    )
    (net (code "298") (name "unconnected-(J5-Pad16)") (class "Default")
      (node (ref "J5") (pin "16") (pintype "passive+no_connect"))
    )
    (net (code "299") (name "unconnected-(J5-Pad17)") (class "Default")
      (node (ref "J5") (pin "17") (pintype "passive+no_connect"))
    )
    (net (code "300") (name "unconnected-(J5-Pad18)") (class "Default")
      (node (ref "J5") (pin "18") (pintype "passive+no_connect"))
    )
    (net (code "301") (name "unconnected-(J5-Pad19)") (class "Default")
      (node (ref "J5") (pin "19") (pintype "passive+no_connect"))
    )
    (net (code "302") (name "unconnected-(J5-Pad20)") (class "Default")
      (node (ref "J5") (pin "20") (pintype "passive+no_connect"))
    )
    (net (code "303") (name "unconnected-(LCD1-IC_CS-Pad11)") (class "Default")
      (node (ref "LCD1") (pin "11") (pinfunction "IC_CS_11") (pintype "passive+no_connect"))
    )
    (net (code "304") (name "unconnected-(LCD1-IC_SC-Pad10)") (class "Default")
      (node (ref "LCD1") (pin "10") (pinfunction "IC_SC_10") (pintype "passive+no_connect"))
    )
    (net (code "305") (name "unconnected-(LCD1-IC_SI-Pad13)") (class "Default")
      (node (ref "LCD1") (pin "13") (pinfunction "IC_SI_13") (pintype "passive+no_connect"))
    )
    (net (code "306") (name "unconnected-(LCD1-IC_SO-Pad12)") (class "Default")
      (node (ref "LCD1") (pin "12") (pinfunction "IC_SO_12") (pintype "passive+no_connect"))
    )
    (net (code "307") (name "unconnected-(U21-RTS#-Pad4)") (class "Default")
      (node (ref "U21") (pin "4") (pinfunction "RTS#_4") (pintype "passive+no_connect"))
    )
    (net (code "308") (name "unconnected-(U24-2A3-Pad33)") (class "Default")
      (node (ref "U24") (pin "33") (pinfunction "2A3_33") (pintype "bidirectional+no_connect"))
    )
    (net (code "309") (name "unconnected-(U24-2A4-Pad32)") (class "Default")
      (node (ref "U24") (pin "32") (pinfunction "2A4_32") (pintype "bidirectional+no_connect"))
    )
    (net (code "310") (name "unconnected-(U24-2A5-Pad30)") (class "Default")
      (node (ref "U24") (pin "30") (pinfunction "2A5_30") (pintype "bidirectional+no_connect"))
    )
    (net (code "311") (name "unconnected-(U24-2A6-Pad29)") (class "Default")
      (node (ref "U24") (pin "29") (pinfunction "2A6_29") (pintype "bidirectional+no_connect"))
    )
    (net (code "312") (name "unconnected-(U24-2A7-Pad27)") (class "Default")
      (node (ref "U24") (pin "27") (pinfunction "2A7_27") (pintype "bidirectional+no_connect"))
    )
    (net (code "313") (name "unconnected-(U24-2A8-Pad26)") (class "Default")
      (node (ref "U24") (pin "26") (pinfunction "2A8_26") (pintype "bidirectional+no_connect"))
    )
    (net (code "314") (name "unconnected-(U24-2B3-Pad16)") (class "Default")
      (node (ref "U24") (pin "16") (pinfunction "2B3_16") (pintype "bidirectional+no_connect"))
    )
    (net (code "315") (name "unconnected-(U24-2B4-Pad17)") (class "Default")
      (node (ref "U24") (pin "17") (pinfunction "2B4_17") (pintype "bidirectional+no_connect"))
    )
    (net (code "316") (name "unconnected-(U24-2B5-Pad19)") (class "Default")
      (node (ref "U24") (pin "19") (pinfunction "2B5_19") (pintype "bidirectional+no_connect"))
    )
    (net (code "317") (name "unconnected-(U24-2B6-Pad20)") (class "Default")
      (node (ref "U24") (pin "20") (pinfunction "2B6_20") (pintype "bidirectional+no_connect"))
    )
    (net (code "318") (name "unconnected-(U24-2B7-Pad22)") (class "Default")
      (node (ref "U24") (pin "22") (pinfunction "2B7_22") (pintype "bidirectional+no_connect"))
    )
    (net (code "319") (name "unconnected-(U24-2B8-Pad23)") (class "Default")
      (node (ref "U24") (pin "23") (pinfunction "2B8_23") (pintype "bidirectional+no_connect"))
    )
  )
)
